# EMG_SS19_Version_1_0.net
KiCad netlist of a schematic drawn in EAGLE
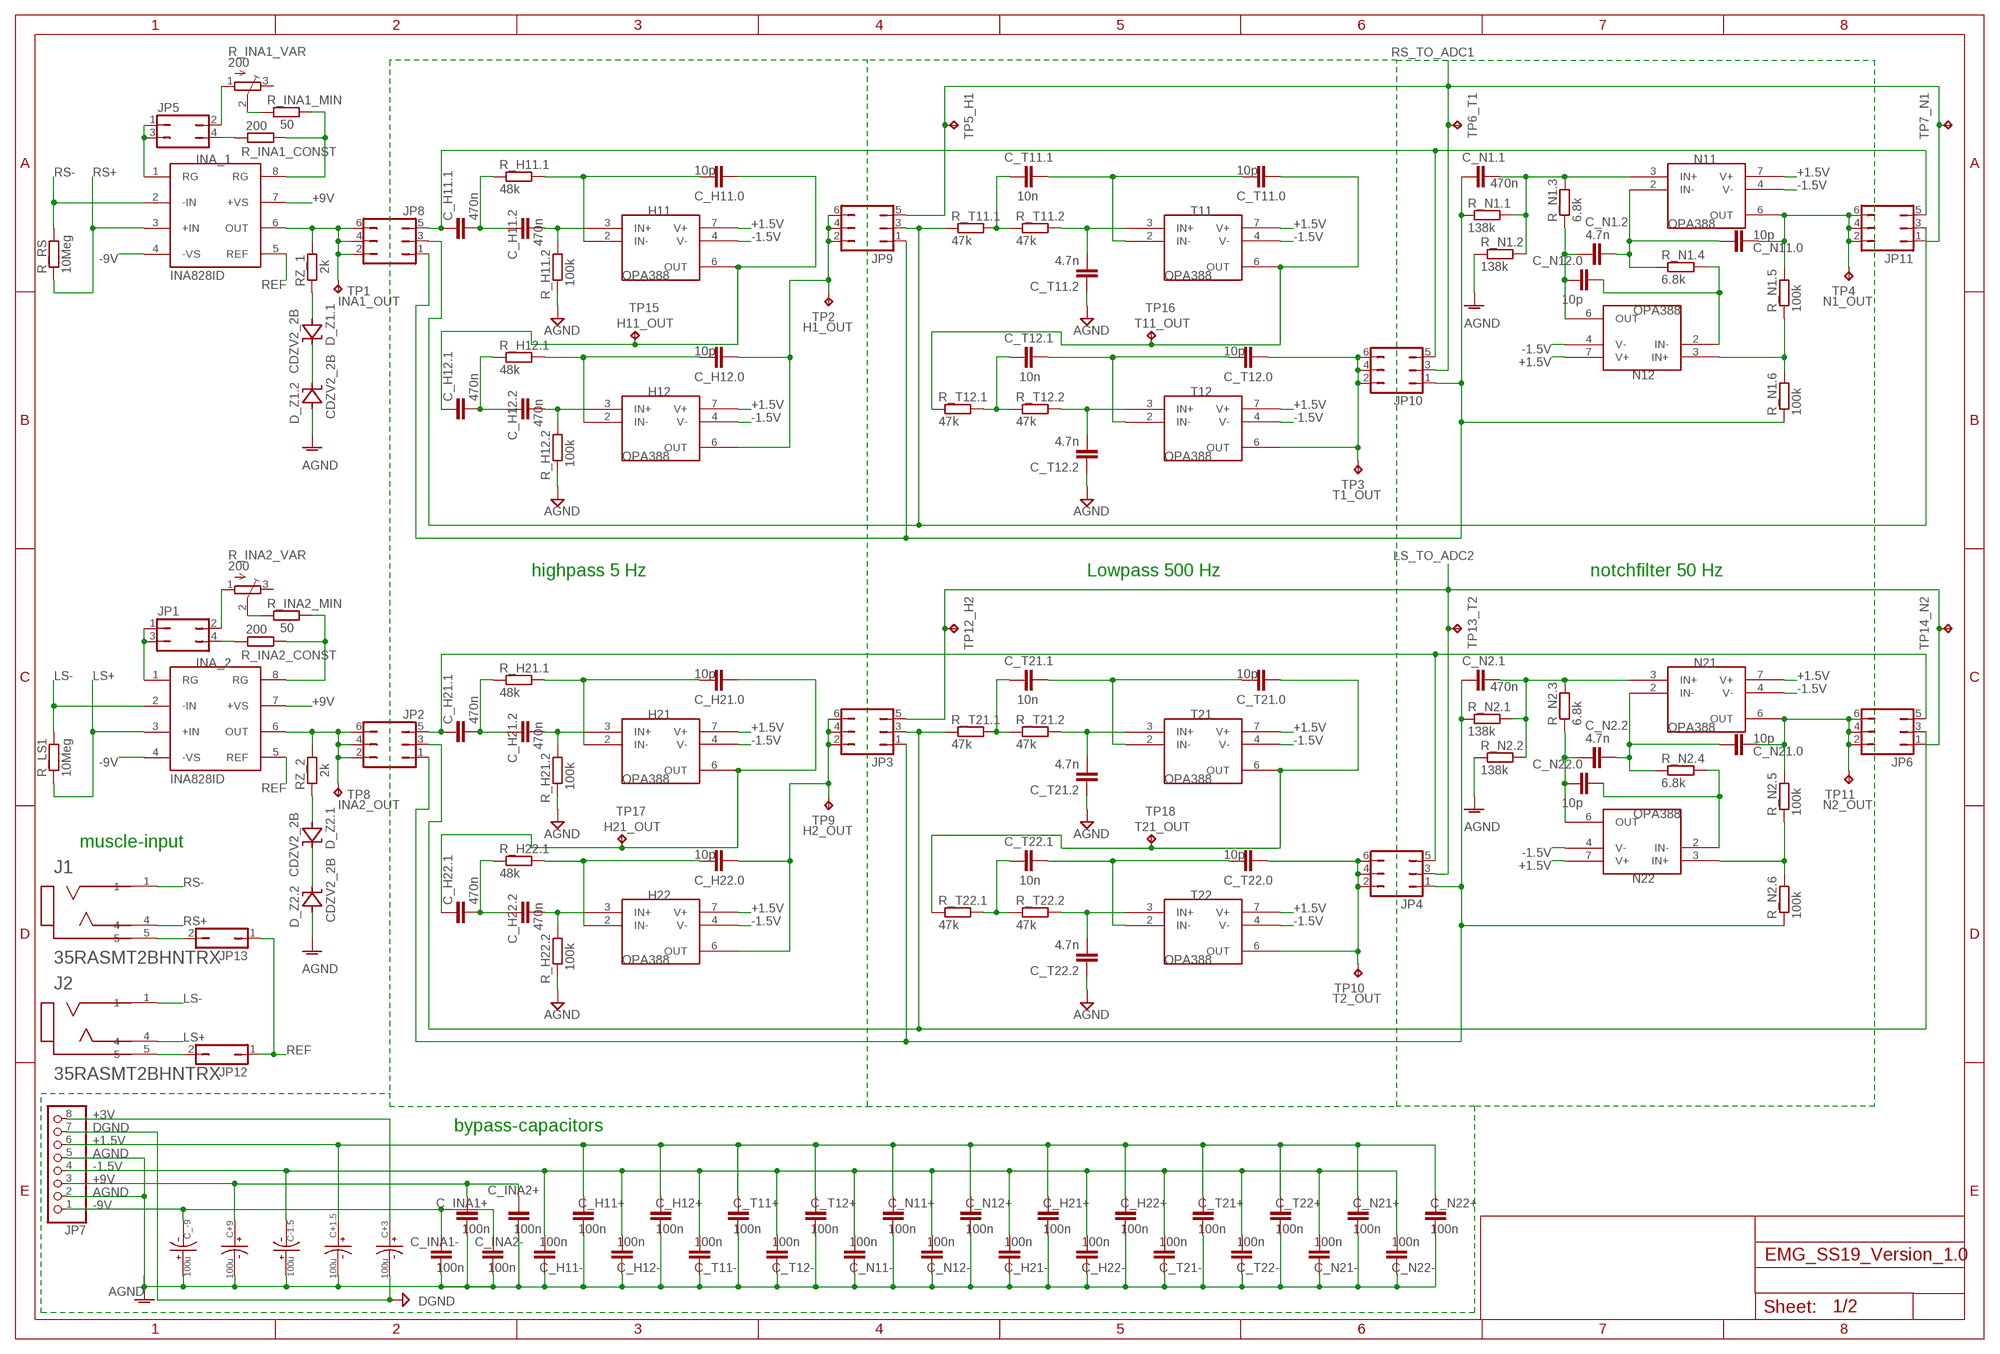
[diagram p0: schematic, sheet 1]
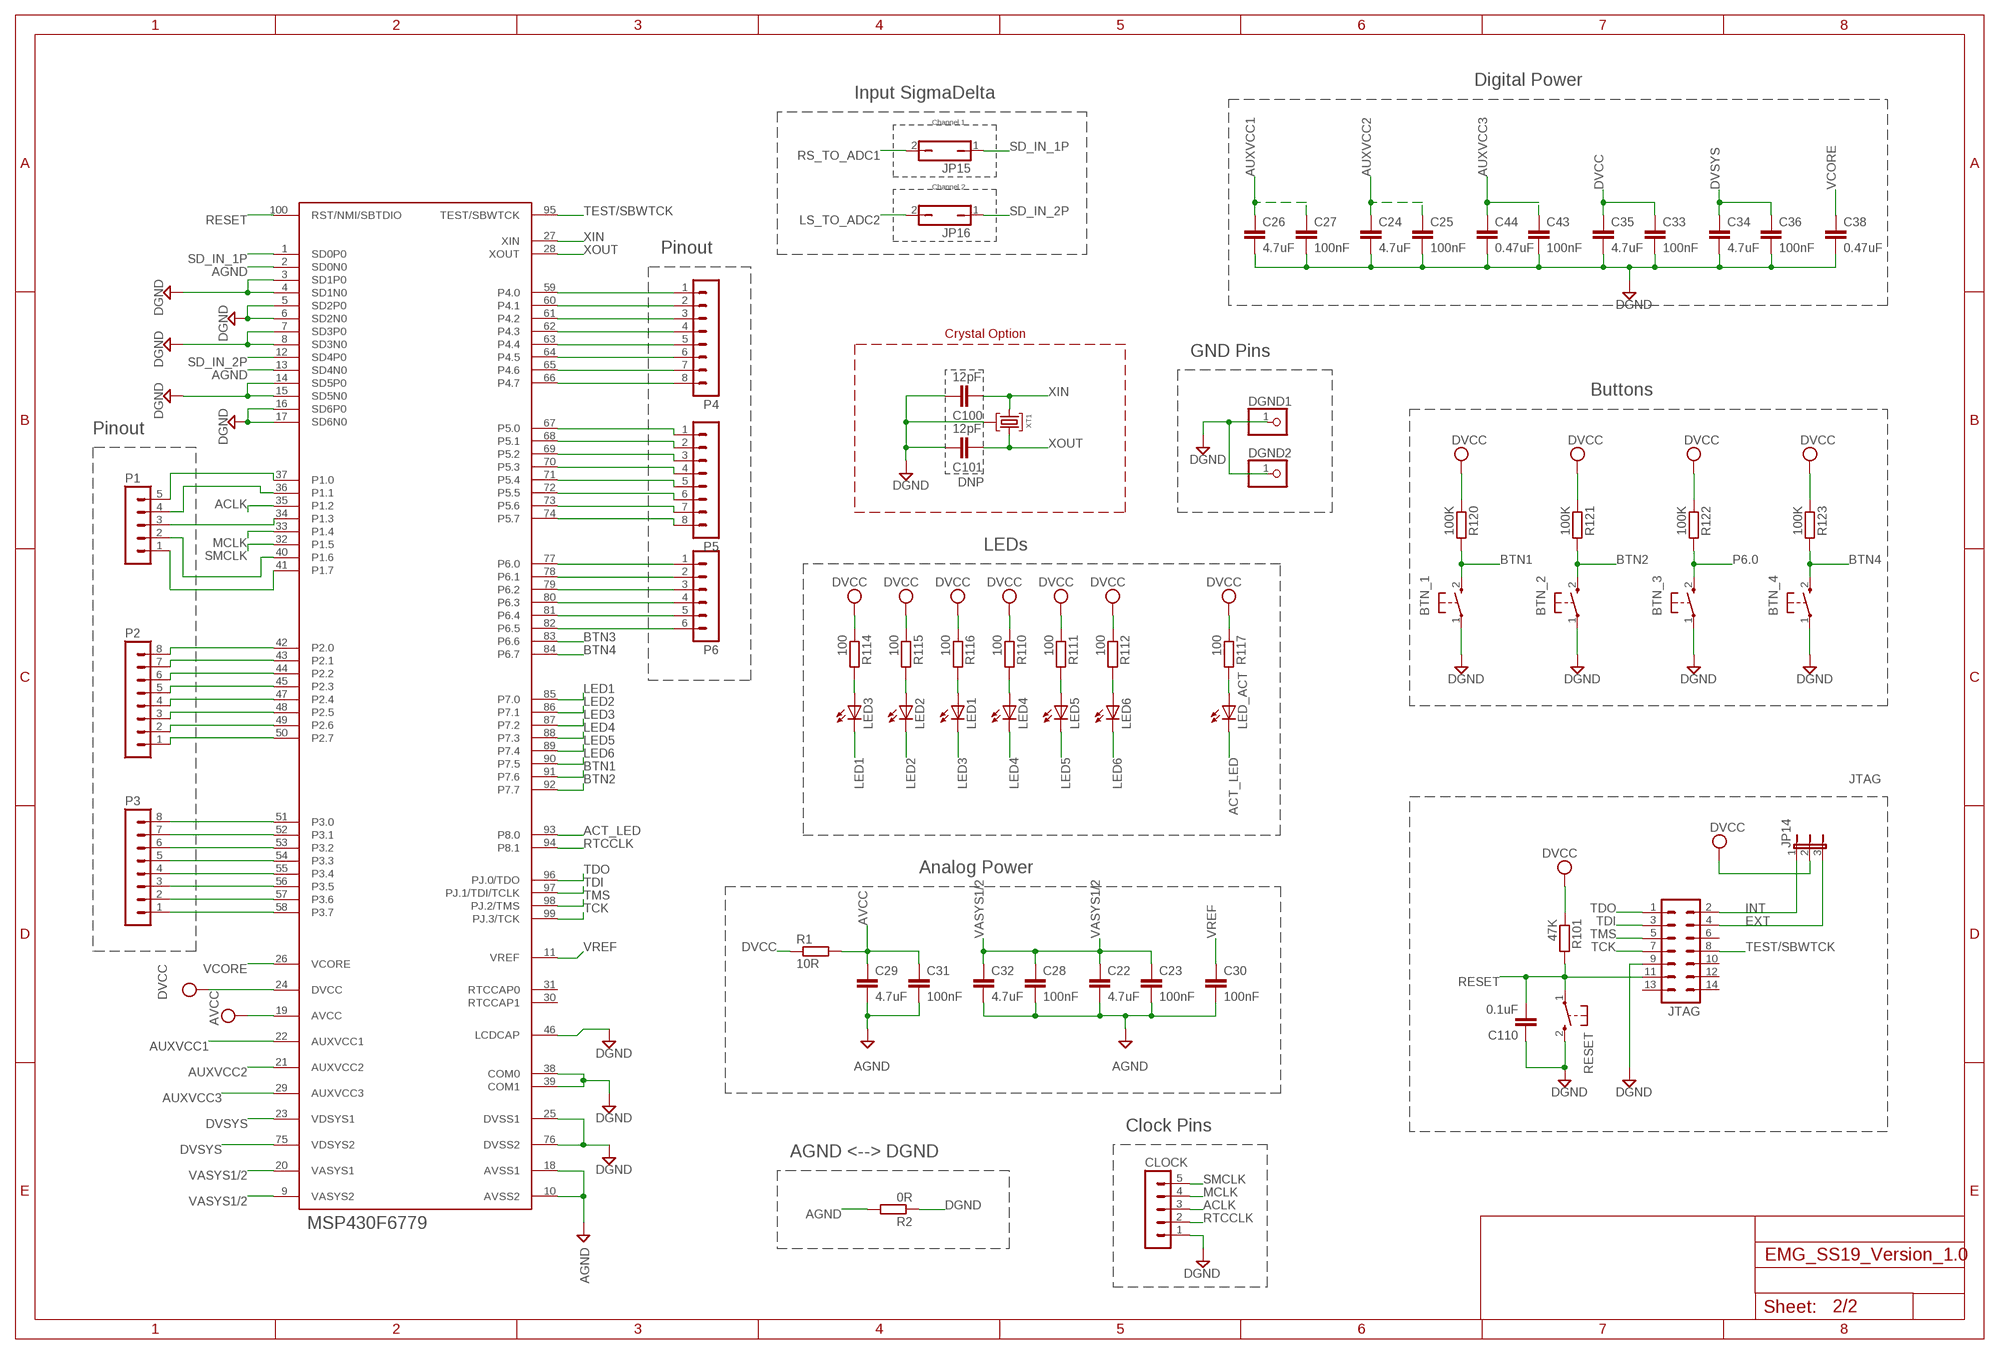
[diagram p1: schematic, sheet 2]

(export (version "E")
  (design (tool "Eeschema 10.0.6"))
  (components
    (comp (ref "C+1.5")
      (value "100u")
      (footprint "eagle-import:CAPPRD350W60D800H1150B")
      (fields (field (name "MF") "Panasonic Electronic") (field (name "MP") "ECA1HM101"))
      (libsource (lib "eagle-import") (part "ECA-1HM101"))
    )
    (comp (ref "C+3")
      (value "100u")
      (footprint "eagle-import:CAPPRD350W60D800H1150B")
      (fields (field (name "MF") "Panasonic Electronic") (field (name "MP") "ECA1HM101"))
      (libsource (lib "eagle-import") (part "ECA-1HM101"))
    )
    (comp (ref "C+9")
      (value "100u")
      (footprint "eagle-import:CAPPRD350W60D800H1150B")
      (fields (field (name "MF") "Panasonic Electronic") (field (name "MP") "ECA1HM101"))
      (libsource (lib "eagle-import") (part "ECA-1HM101"))
    )
    (comp (ref "C-1.5")
      (value "100u")
      (footprint "eagle-import:CAPPRD350W60D800H1150B")
      (fields (field (name "MF") "Panasonic Electronic") (field (name "MP") "ECA1HM101"))
      (libsource (lib "eagle-import") (part "ECA-1HM101"))
    )
    (comp (ref "C_-9")
      (value "100u")
      (footprint "eagle-import:CAPPRD350W60D800H1150B")
      (fields (field (name "MF") "Panasonic Electronic") (field (name "MP") "ECA1HM101"))
      (libsource (lib "eagle-import") (part "ECA-1HM101"))
    )
    (comp (ref "C_H11+")
      (value "100n")
      (footprint "eagle-import:C0805")
      (libsource (lib "eagle-import") (part "C-EUC0805"))
    )
    (comp (ref "C_H11-")
      (value "100n")
      (footprint "eagle-import:C0805")
      (libsource (lib "eagle-import") (part "C-EUC0805"))
    )
    (comp (ref "C_H11.0")
      (value "10p")
      (footprint "eagle-import:C0805")
      (libsource (lib "eagle-import") (part "C-EUC0805"))
    )
    (comp (ref "C_H11.1")
      (value "470n")
      (footprint "eagle-import:C0805")
      (libsource (lib "eagle-import") (part "C-EUC0805"))
    )
    (comp (ref "C_H11.2")
      (value "470n")
      (footprint "eagle-import:C0805")
      (libsource (lib "eagle-import") (part "C-EUC0805"))
    )
    (comp (ref "C_H12+")
      (value "100n")
      (footprint "eagle-import:C0805")
      (libsource (lib "eagle-import") (part "C-EUC0805"))
    )
    (comp (ref "C_H12-")
      (value "100n")
      (footprint "eagle-import:C0805")
      (libsource (lib "eagle-import") (part "C-EUC0805"))
    )
    (comp (ref "C_H12.0")
      (value "10p")
      (footprint "eagle-import:C0805")
      (libsource (lib "eagle-import") (part "C-EUC0805"))
    )
    (comp (ref "C_H12.1")
      (value "470n")
      (footprint "eagle-import:C0805")
      (libsource (lib "eagle-import") (part "C-EUC0805"))
    )
    (comp (ref "C_H12.2")
      (value "470n")
      (footprint "eagle-import:C0805")
      (libsource (lib "eagle-import") (part "C-EUC0805"))
    )
    (comp (ref "C_H21+")
      (value "100n")
      (footprint "eagle-import:C0805")
      (libsource (lib "eagle-import") (part "C-EUC0805"))
    )
    (comp (ref "C_H21-")
      (value "100n")
      (footprint "eagle-import:C0805")
      (libsource (lib "eagle-import") (part "C-EUC0805"))
    )
    (comp (ref "C_H21.0")
      (value "10p")
      (footprint "eagle-import:C0805")
      (libsource (lib "eagle-import") (part "C-EUC0805"))
    )
    (comp (ref "C_H21.1")
      (value "470n")
      (footprint "eagle-import:C0805")
      (libsource (lib "eagle-import") (part "C-EUC0805"))
    )
    (comp (ref "C_H21.2")
      (value "470n")
      (footprint "eagle-import:C0805")
      (libsource (lib "eagle-import") (part "C-EUC0805"))
    )
    (comp (ref "C_H22+")
      (value "100n")
      (footprint "eagle-import:C0805")
      (libsource (lib "eagle-import") (part "C-EUC0805"))
    )
    (comp (ref "C_H22-")
      (value "100n")
      (footprint "eagle-import:C0805")
      (libsource (lib "eagle-import") (part "C-EUC0805"))
    )
    (comp (ref "C_H22.0")
      (value "10p")
      (footprint "eagle-import:C0805")
      (libsource (lib "eagle-import") (part "C-EUC0805"))
    )
    (comp (ref "C_H22.1")
      (value "470n")
      (footprint "eagle-import:C0805")
      (libsource (lib "eagle-import") (part "C-EUC0805"))
    )
    (comp (ref "C_H22.2")
      (value "470n")
      (footprint "eagle-import:C0805")
      (libsource (lib "eagle-import") (part "C-EUC0805"))
    )
    (comp (ref "C_INA1+")
      (value "100n")
      (footprint "eagle-import:C0805")
      (libsource (lib "eagle-import") (part "C-EUC0805"))
    )
    (comp (ref "C_INA1-")
      (value "100n")
      (footprint "eagle-import:C0805")
      (libsource (lib "eagle-import") (part "C-EUC0805"))
    )
    (comp (ref "C_INA2+")
      (value "100n")
      (footprint "eagle-import:C0805")
      (libsource (lib "eagle-import") (part "C-EUC0805"))
    )
    (comp (ref "C_INA2-")
      (value "100n")
      (footprint "eagle-import:C0805")
      (libsource (lib "eagle-import") (part "C-EUC0805"))
    )
    (comp (ref "C_N1.1")
      (value "470n")
      (footprint "eagle-import:C0805")
      (libsource (lib "eagle-import") (part "C-EUC0805"))
    )
    (comp (ref "C_N1.2")
      (value "4.7n")
      (footprint "eagle-import:C0805")
      (libsource (lib "eagle-import") (part "C-EUC0805"))
    )
    (comp (ref "C_N2.1")
      (value "470n")
      (footprint "eagle-import:C0805")
      (libsource (lib "eagle-import") (part "C-EUC0805"))
    )
    (comp (ref "C_N2.2")
      (value "4.7n")
      (footprint "eagle-import:C0805")
      (libsource (lib "eagle-import") (part "C-EUC0805"))
    )
    (comp (ref "C_N11+")
      (value "100n")
      (footprint "eagle-import:C0805")
      (libsource (lib "eagle-import") (part "C-EUC0805"))
    )
    (comp (ref "C_N11-")
      (value "100n")
      (footprint "eagle-import:C0805")
      (libsource (lib "eagle-import") (part "C-EUC0805"))
    )
    (comp (ref "C_N11.0")
      (value "10p")
      (footprint "eagle-import:C0805")
      (libsource (lib "eagle-import") (part "C-EUC0805"))
    )
    (comp (ref "C_N12+")
      (value "100n")
      (footprint "eagle-import:C0805")
      (libsource (lib "eagle-import") (part "C-EUC0805"))
    )
    (comp (ref "C_N12-")
      (value "100n")
      (footprint "eagle-import:C0805")
      (libsource (lib "eagle-import") (part "C-EUC0805"))
    )
    (comp (ref "C_N12.0")
      (value "10p")
      (footprint "eagle-import:C0805")
      (libsource (lib "eagle-import") (part "C-EUC0805"))
    )
    (comp (ref "C_N21+")
      (value "100n")
      (footprint "eagle-import:C0805")
      (libsource (lib "eagle-import") (part "C-EUC0805"))
    )
    (comp (ref "C_N21-")
      (value "100n")
      (footprint "eagle-import:C0805")
      (libsource (lib "eagle-import") (part "C-EUC0805"))
    )
    (comp (ref "C_N21.0")
      (value "10p")
      (footprint "eagle-import:C0805")
      (libsource (lib "eagle-import") (part "C-EUC0805"))
    )
    (comp (ref "C_N22+")
      (value "100n")
      (footprint "eagle-import:C0805")
      (libsource (lib "eagle-import") (part "C-EUC0805"))
    )
    (comp (ref "C_N22-")
      (value "100n")
      (footprint "eagle-import:C0805")
      (libsource (lib "eagle-import") (part "C-EUC0805"))
    )
    (comp (ref "C_N22.0")
      (value "10p")
      (footprint "eagle-import:C0805")
      (libsource (lib "eagle-import") (part "C-EUC0805"))
    )
    (comp (ref "C_T11+")
      (value "100n")
      (footprint "eagle-import:C0805")
      (libsource (lib "eagle-import") (part "C-EUC0805"))
    )
    (comp (ref "C_T11-")
      (value "100n")
      (footprint "eagle-import:C0805")
      (libsource (lib "eagle-import") (part "C-EUC0805"))
    )
    (comp (ref "C_T11.0")
      (value "10p")
      (footprint "eagle-import:C0805")
      (libsource (lib "eagle-import") (part "C-EUC0805"))
    )
    (comp (ref "C_T11.1")
      (value "10n")
      (footprint "eagle-import:C0805")
      (libsource (lib "eagle-import") (part "C-EUC0805"))
    )
    (comp (ref "C_T11.2")
      (value "4.7n")
      (footprint "eagle-import:C0805")
      (libsource (lib "eagle-import") (part "C-EUC0805"))
    )
    (comp (ref "C_T12+")
      (value "100n")
      (footprint "eagle-import:C0805")
      (libsource (lib "eagle-import") (part "C-EUC0805"))
    )
    (comp (ref "C_T12-")
      (value "100n")
      (footprint "eagle-import:C0805")
      (libsource (lib "eagle-import") (part "C-EUC0805"))
    )
    (comp (ref "C_T12.0")
      (value "10p")
      (footprint "eagle-import:C0805")
      (libsource (lib "eagle-import") (part "C-EUC0805"))
    )
    (comp (ref "C_T12.1")
      (value "10n")
      (footprint "eagle-import:C0805")
      (libsource (lib "eagle-import") (part "C-EUC0805"))
    )
    (comp (ref "C_T12.2")
      (value "4.7n")
      (footprint "eagle-import:C0805")
      (libsource (lib "eagle-import") (part "C-EUC0805"))
    )
    (comp (ref "C_T21+")
      (value "100n")
      (footprint "eagle-import:C0805")
      (libsource (lib "eagle-import") (part "C-EUC0805"))
    )
    (comp (ref "C_T21-")
      (value "100n")
      (footprint "eagle-import:C0805")
      (libsource (lib "eagle-import") (part "C-EUC0805"))
    )
    (comp (ref "C_T21.0")
      (value "10p")
      (footprint "eagle-import:C0805")
      (libsource (lib "eagle-import") (part "C-EUC0805"))
    )
    (comp (ref "C_T21.1")
      (value "10n")
      (footprint "eagle-import:C0805")
      (libsource (lib "eagle-import") (part "C-EUC0805"))
    )
    (comp (ref "C_T21.2")
      (value "4.7n")
      (footprint "eagle-import:C0805")
      (libsource (lib "eagle-import") (part "C-EUC0805"))
    )
    (comp (ref "C_T22+")
      (value "100n")
      (footprint "eagle-import:C0805")
      (libsource (lib "eagle-import") (part "C-EUC0805"))
    )
    (comp (ref "C_T22-")
      (value "100n")
      (footprint "eagle-import:C0805")
      (libsource (lib "eagle-import") (part "C-EUC0805"))
    )
    (comp (ref "C_T22.0")
      (value "10p")
      (footprint "eagle-import:C0805")
      (libsource (lib "eagle-import") (part "C-EUC0805"))
    )
    (comp (ref "C_T22.1")
      (value "10n")
      (footprint "eagle-import:C0805")
      (libsource (lib "eagle-import") (part "C-EUC0805"))
    )
    (comp (ref "C_T22.2")
      (value "4.7n")
      (footprint "eagle-import:C0805")
      (libsource (lib "eagle-import") (part "C-EUC0805"))
    )
    (comp (ref "D_Z1.1")
      (value "CDZV2_2B")
      (footprint "eagle-import:SODFL1006X40N")
      (libsource (lib "eagle-import") (part "CDZV2_2BSOD923"))
    )
    (comp (ref "D_Z1.2")
      (value "CDZV2_2B")
      (footprint "eagle-import:SODFL1006X40N")
      (libsource (lib "eagle-import") (part "CDZV2_2BSOD923"))
    )
    (comp (ref "D_Z2.1")
      (value "CDZV2_2B")
      (footprint "eagle-import:SODFL1006X40N")
      (libsource (lib "eagle-import") (part "CDZV2_2BSOD923"))
    )
    (comp (ref "D_Z2.2")
      (value "CDZV2_2B")
      (footprint "eagle-import:SODFL1006X40N")
      (libsource (lib "eagle-import") (part "CDZV2_2BSOD923"))
    )
    (comp (ref "H11")
      (value "OPA388")
      (footprint "eagle-import:SOIC127P600X175-8N")
      (libsource (lib "eagle-import") (part "OPA388"))
    )
    (comp (ref "H12")
      (value "OPA388")
      (footprint "eagle-import:SOIC127P600X175-8N")
      (libsource (lib "eagle-import") (part "OPA388"))
    )
    (comp (ref "H21")
      (value "OPA388")
      (footprint "eagle-import:SOIC127P600X175-8N")
      (libsource (lib "eagle-import") (part "OPA388"))
    )
    (comp (ref "H22")
      (value "OPA388")
      (footprint "eagle-import:SOIC127P600X175-8N")
      (libsource (lib "eagle-import") (part "OPA388"))
    )
    (comp (ref "INA_1")
      (value "INA828ID")
      (footprint "eagle-import:SOIC8")
      (fields (field (name "DIGI-KEY_PART_NUMBER") "296-47415-ND") (field (name "MF") "Texas Instruments"))
      (libsource (lib "eagle-import") (part "INA828ID"))
    )
    (comp (ref "INA_2")
      (value "INA828ID")
      (footprint "eagle-import:SOIC8")
      (fields (field (name "DIGI-KEY_PART_NUMBER") "296-47415-ND") (field (name "MF") "Texas Instruments"))
      (libsource (lib "eagle-import") (part "INA828ID"))
    )
    (comp (ref "J1")
      (value "35RASMT2BHNTRX")
      (footprint "eagle-import:SWITCHCRAFT_35RASMT2BHNTRX")
      (fields (field (name "MF") "Switchcraft"))
      (libsource (lib "eagle-import") (part "35RASMT2BHNTRX"))
    )
    (comp (ref "J2")
      (value "35RASMT2BHNTRX")
      (footprint "eagle-import:SWITCHCRAFT_35RASMT2BHNTRX")
      (fields (field (name "MF") "Switchcraft"))
      (libsource (lib "eagle-import") (part "35RASMT2BHNTRX"))
    )
    (comp (ref "JP1")
      (value "JP2Q")
      (footprint "eagle-import:JP2Q")
      (libsource (lib "eagle-import") (part "JP2Q"))
    )
    (comp (ref "JP2")
      (value "JP3Q")
      (footprint "eagle-import:JP3Q")
      (libsource (lib "eagle-import") (part "JP3Q"))
    )
    (comp (ref "JP3")
      (value "JP3Q")
      (footprint "eagle-import:JP3Q")
      (libsource (lib "eagle-import") (part "JP3Q"))
    )
    (comp (ref "JP4")
      (value "JP3Q")
      (footprint "eagle-import:JP3Q")
      (libsource (lib "eagle-import") (part "JP3Q"))
    )
    (comp (ref "JP5")
      (value "JP2Q")
      (footprint "eagle-import:JP2Q")
      (libsource (lib "eagle-import") (part "JP2Q"))
    )
    (comp (ref "JP6")
      (value "JP3Q")
      (footprint "eagle-import:JP3Q")
      (libsource (lib "eagle-import") (part "JP3Q"))
    )
    (comp (ref "JP7")
      (value "PINHD-1X8")
      (footprint "eagle-import:1X08")
      (libsource (lib "eagle-import") (part "PINHD-1X8"))
    )
    (comp (ref "JP8")
      (value "JP3Q")
      (footprint "eagle-import:JP3Q")
      (libsource (lib "eagle-import") (part "JP3Q"))
    )
    (comp (ref "JP9")
      (value "JP3Q")
      (footprint "eagle-import:JP3Q")
      (libsource (lib "eagle-import") (part "JP3Q"))
    )
    (comp (ref "JP10")
      (value "JP3Q")
      (footprint "eagle-import:JP3Q")
      (libsource (lib "eagle-import") (part "JP3Q"))
    )
    (comp (ref "JP11")
      (value "JP3Q")
      (footprint "eagle-import:JP3Q")
      (libsource (lib "eagle-import") (part "JP3Q"))
    )
    (comp (ref "JP12")
      (value "JP1Q")
      (footprint "eagle-import:JP1")
      (libsource (lib "eagle-import") (part "JP1Q"))
    )
    (comp (ref "JP13")
      (value "JP1Q")
      (footprint "eagle-import:JP1")
      (libsource (lib "eagle-import") (part "JP1Q"))
    )
    (comp (ref "N11")
      (value "OPA388")
      (footprint "eagle-import:SOIC127P600X175-8N")
      (libsource (lib "eagle-import") (part "OPA388"))
    )
    (comp (ref "N12")
      (value "OPA388")
      (footprint "eagle-import:SOIC127P600X175-8N")
      (libsource (lib "eagle-import") (part "OPA388"))
    )
    (comp (ref "N21")
      (value "OPA388")
      (footprint "eagle-import:SOIC127P600X175-8N")
      (libsource (lib "eagle-import") (part "OPA388"))
    )
    (comp (ref "N22")
      (value "OPA388")
      (footprint "eagle-import:SOIC127P600X175-8N")
      (libsource (lib "eagle-import") (part "OPA388"))
    )
    (comp (ref "RZ_1")
      (value "2k")
      (footprint "eagle-import:R0805")
      (libsource (lib "eagle-import") (part "R-EU_R0805"))
    )
    (comp (ref "RZ_2")
      (value "2k")
      (footprint "eagle-import:R0805")
      (libsource (lib "eagle-import") (part "R-EU_R0805"))
    )
    (comp (ref "R_H11.1")
      (value "48k")
      (footprint "eagle-import:R0805")
      (libsource (lib "eagle-import") (part "R-EU_R0805"))
    )
    (comp (ref "R_H11.2")
      (value "100k")
      (footprint "eagle-import:R0805")
      (libsource (lib "eagle-import") (part "R-EU_R0805"))
    )
    (comp (ref "R_H12.1")
      (value "48k")
      (footprint "eagle-import:R0805")
      (libsource (lib "eagle-import") (part "R-EU_R0805"))
    )
    (comp (ref "R_H12.2")
      (value "100k")
      (footprint "eagle-import:R0805")
      (libsource (lib "eagle-import") (part "R-EU_R0805"))
    )
    (comp (ref "R_H21.1")
      (value "48k")
      (footprint "eagle-import:R0805")
      (libsource (lib "eagle-import") (part "R-EU_R0805"))
    )
    (comp (ref "R_H21.2")
      (value "100k")
      (footprint "eagle-import:R0805")
      (libsource (lib "eagle-import") (part "R-EU_R0805"))
    )
    (comp (ref "R_H22.1")
      (value "48k")
      (footprint "eagle-import:R0805")
      (libsource (lib "eagle-import") (part "R-EU_R0805"))
    )
    (comp (ref "R_H22.2")
      (value "100k")
      (footprint "eagle-import:R0805")
      (libsource (lib "eagle-import") (part "R-EU_R0805"))
    )
    (comp (ref "R_INA1_CONST")
      (value "200")
      (footprint "eagle-import:R0805")
      (libsource (lib "eagle-import") (part "R-EU_R0805"))
    )
    (comp (ref "R_INA1_MIN")
      (value "50")
      (footprint "eagle-import:R0805")
      (libsource (lib "eagle-import") (part "R-EU_R0805"))
    )
    (comp (ref "R_INA1_VAR")
      (value "200")
      (footprint "eagle-import:SM-42_43W")
      (fields (field (name "SPICEPREFIX") "J"))
      (libsource (lib "eagle-import") (part "TRIM_EU-SM-42/43W"))
    )
    (comp (ref "R_INA2_CONST")
      (value "200")
      (footprint "eagle-import:R0805")
      (libsource (lib "eagle-import") (part "R-EU_R0805"))
    )
    (comp (ref "R_INA2_MIN")
      (value "50")
      (footprint "eagle-import:R0805")
      (libsource (lib "eagle-import") (part "R-EU_R0805"))
    )
    (comp (ref "R_INA2_VAR")
      (value "200")
      (footprint "eagle-import:SM-42_43W")
      (fields (field (name "SPICEPREFIX") "J"))
      (libsource (lib "eagle-import") (part "TRIM_EU-SM-42/43W"))
    )
    (comp (ref "R_LS1")
      (value "10Meg")
      (footprint "eagle-import:R0805")
      (libsource (lib "eagle-import") (part "R-EU_R0805"))
    )
    (comp (ref "R_N1.1")
      (value "138k")
      (footprint "eagle-import:R0805")
      (libsource (lib "eagle-import") (part "R-EU_R0805"))
    )
    (comp (ref "R_N1.2")
      (value "138k")
      (footprint "eagle-import:R0805")
      (libsource (lib "eagle-import") (part "R-EU_R0805"))
    )
    (comp (ref "R_N1.3")
      (value "6.8k")
      (footprint "eagle-import:R0805")
      (libsource (lib "eagle-import") (part "R-EU_R0805"))
    )
    (comp (ref "R_N1.4")
      (value "6.8k")
      (footprint "eagle-import:R0805")
      (libsource (lib "eagle-import") (part "R-EU_R0805"))
    )
    (comp (ref "R_N1.5")
      (value "100k")
      (footprint "eagle-import:R0805")
      (libsource (lib "eagle-import") (part "R-EU_R0805"))
    )
    (comp (ref "R_N1.6")
      (value "100k")
      (footprint "eagle-import:R0805")
      (libsource (lib "eagle-import") (part "R-EU_R0805"))
    )
    (comp (ref "R_N2.1")
      (value "138k")
      (footprint "eagle-import:R0805")
      (libsource (lib "eagle-import") (part "R-EU_R0805"))
    )
    (comp (ref "R_N2.2")
      (value "138k")
      (footprint "eagle-import:R0805")
      (libsource (lib "eagle-import") (part "R-EU_R0805"))
    )
    (comp (ref "R_N2.3")
      (value "6.8k")
      (footprint "eagle-import:R0805")
      (libsource (lib "eagle-import") (part "R-EU_R0805"))
    )
    (comp (ref "R_N2.4")
      (value "6.8k")
      (footprint "eagle-import:R0805")
      (libsource (lib "eagle-import") (part "R-EU_R0805"))
    )
    (comp (ref "R_N2.5")
      (value "100k")
      (footprint "eagle-import:R0805")
      (libsource (lib "eagle-import") (part "R-EU_R0805"))
    )
    (comp (ref "R_N2.6")
      (value "100k")
      (footprint "eagle-import:R0805")
      (libsource (lib "eagle-import") (part "R-EU_R0805"))
    )
    (comp (ref "R_RS")
      (value "10Meg")
      (footprint "eagle-import:R0805")
      (libsource (lib "eagle-import") (part "R-EU_R0805"))
    )
    (comp (ref "R_T11.1")
      (value "47k")
      (footprint "eagle-import:R0805")
      (libsource (lib "eagle-import") (part "R-EU_R0805"))
    )
    (comp (ref "R_T11.2")
      (value "47k")
      (footprint "eagle-import:R0805")
      (libsource (lib "eagle-import") (part "R-EU_R0805"))
    )
    (comp (ref "R_T12.1")
      (value "47k")
      (footprint "eagle-import:R0805")
      (libsource (lib "eagle-import") (part "R-EU_R0805"))
    )
    (comp (ref "R_T12.2")
      (value "47k")
      (footprint "eagle-import:R0805")
      (libsource (lib "eagle-import") (part "R-EU_R0805"))
    )
    (comp (ref "R_T21.1")
      (value "47k")
      (footprint "eagle-import:R0805")
      (libsource (lib "eagle-import") (part "R-EU_R0805"))
    )
    (comp (ref "R_T21.2")
      (value "47k")
      (footprint "eagle-import:R0805")
      (libsource (lib "eagle-import") (part "R-EU_R0805"))
    )
    (comp (ref "R_T22.1")
      (value "47k")
      (footprint "eagle-import:R0805")
      (libsource (lib "eagle-import") (part "R-EU_R0805"))
    )
    (comp (ref "R_T22.2")
      (value "47k")
      (footprint "eagle-import:R0805")
      (libsource (lib "eagle-import") (part "R-EU_R0805"))
    )
    (comp (ref "T11")
      (value "OPA388")
      (footprint "eagle-import:SOIC127P600X175-8N")
      (libsource (lib "eagle-import") (part "OPA388"))
    )
    (comp (ref "T12")
      (value "OPA388")
      (footprint "eagle-import:SOIC127P600X175-8N")
      (libsource (lib "eagle-import") (part "OPA388"))
    )
    (comp (ref "T21")
      (value "OPA388")
      (footprint "eagle-import:SOIC127P600X175-8N")
      (libsource (lib "eagle-import") (part "OPA388"))
    )
    (comp (ref "T22")
      (value "OPA388")
      (footprint "eagle-import:SOIC127P600X175-8N")
      (libsource (lib "eagle-import") (part "OPA388"))
    )
    (comp (ref "TP1")
      (value "TPPAD1-13")
      (footprint "eagle-import:P1-13")
      (libsource (lib "eagle-import") (part "TPPAD1-13"))
    )
    (comp (ref "TP2")
      (value "TPPAD1-13")
      (footprint "eagle-import:P1-13")
      (libsource (lib "eagle-import") (part "TPPAD1-13"))
    )
    (comp (ref "TP3")
      (value "TPPAD1-13")
      (footprint "eagle-import:P1-13")
      (libsource (lib "eagle-import") (part "TPPAD1-13"))
    )
    (comp (ref "TP4")
      (value "TPPAD1-13")
      (footprint "eagle-import:P1-13")
      (libsource (lib "eagle-import") (part "TPPAD1-13"))
    )
    (comp (ref "TP5_H1")
      (value "TPPAD1-13")
      (footprint "eagle-import:P1-13")
      (libsource (lib "eagle-import") (part "TPPAD1-13"))
    )
    (comp (ref "TP6_T1")
      (value "TPPAD1-13")
      (footprint "eagle-import:P1-13")
      (libsource (lib "eagle-import") (part "TPPAD1-13"))
    )
    (comp (ref "TP7_N1")
      (value "TPPAD1-13")
      (footprint "eagle-import:P1-13")
      (libsource (lib "eagle-import") (part "TPPAD1-13"))
    )
    (comp (ref "TP8")
      (value "TPPAD1-13")
      (footprint "eagle-import:P1-13")
      (libsource (lib "eagle-import") (part "TPPAD1-13"))
    )
    (comp (ref "TP9")
      (value "TPPAD1-13")
      (footprint "eagle-import:P1-13")
      (libsource (lib "eagle-import") (part "TPPAD1-13"))
    )
    (comp (ref "TP10")
      (value "TPPAD1-13")
      (footprint "eagle-import:P1-13")
      (libsource (lib "eagle-import") (part "TPPAD1-13"))
    )
    (comp (ref "TP11")
      (value "TPPAD1-13")
      (footprint "eagle-import:P1-13")
      (libsource (lib "eagle-import") (part "TPPAD1-13"))
    )
    (comp (ref "TP12_H2")
      (value "TPPAD1-13")
      (footprint "eagle-import:P1-13")
      (libsource (lib "eagle-import") (part "TPPAD1-13"))
    )
    (comp (ref "TP13_T2")
      (value "TPPAD1-13")
      (footprint "eagle-import:P1-13")
      (libsource (lib "eagle-import") (part "TPPAD1-13"))
    )
    (comp (ref "TP14_N2")
      (value "TPPAD1-13")
      (footprint "eagle-import:P1-13")
      (libsource (lib "eagle-import") (part "TPPAD1-13"))
    )
    (comp (ref "TP15")
      (value "TPPAD1-13")
      (footprint "eagle-import:P1-13")
      (libsource (lib "eagle-import") (part "TPPAD1-13"))
    )
    (comp (ref "TP16")
      (value "TPPAD1-13")
      (footprint "eagle-import:P1-13")
      (libsource (lib "eagle-import") (part "TPPAD1-13"))
    )
    (comp (ref "TP17")
      (value "TPPAD1-13")
      (footprint "eagle-import:P1-13")
      (libsource (lib "eagle-import") (part "TPPAD1-13"))
    )
    (comp (ref "TP18")
      (value "TPPAD1-13")
      (footprint "eagle-import:P1-13")
      (libsource (lib "eagle-import") (part "TPPAD1-13"))
    )
    (comp (ref "BTN_1")
      (value "PB")
      (footprint "eagle-import:PBTH")
      (libsource (lib "eagle-import") (part "PB"))
    )
    (comp (ref "BTN_2")
      (value "PB")
      (footprint "eagle-import:PBTH")
      (libsource (lib "eagle-import") (part "PB"))
    )
    (comp (ref "BTN_3")
      (value "PB")
      (footprint "eagle-import:PBTH")
      (libsource (lib "eagle-import") (part "PB"))
    )
    (comp (ref "BTN_4")
      (value "PB")
      (footprint "eagle-import:PBTH")
      (libsource (lib "eagle-import") (part "PB"))
    )
    (comp (ref "C22")
      (value "4.7uF")
      (footprint "eagle-import:C0805")
      (libsource (lib "eagle-import") (part "resistor_C-EUC0805"))
    )
    (comp (ref "C23")
      (value "100nF")
      (footprint "eagle-import:C0805")
      (libsource (lib "eagle-import") (part "resistor_C-EUC0805"))
    )
    (comp (ref "C24")
      (value "4.7uF")
      (footprint "eagle-import:C0805")
      (libsource (lib "eagle-import") (part "resistor_C-EUC0805"))
    )
    (comp (ref "C25")
      (value "100nF")
      (footprint "eagle-import:C0805")
      (libsource (lib "eagle-import") (part "resistor_C-EUC0805"))
    )
    (comp (ref "C26")
      (value "4.7uF")
      (footprint "eagle-import:C0805")
      (libsource (lib "eagle-import") (part "resistor_C-EUC0805"))
    )
    (comp (ref "C27")
      (value "100nF")
      (footprint "eagle-import:C0805")
      (libsource (lib "eagle-import") (part "resistor_C-EUC0805"))
    )
    (comp (ref "C28")
      (value "100nF")
      (footprint "eagle-import:C0805")
      (libsource (lib "eagle-import") (part "resistor_C-EUC0805"))
    )
    (comp (ref "C29")
      (value "4.7uF")
      (footprint "eagle-import:C0805")
      (libsource (lib "eagle-import") (part "resistor_C-EUC0805"))
    )
    (comp (ref "C30")
      (value "100nF")
      (footprint "eagle-import:C0805")
      (libsource (lib "eagle-import") (part "resistor_C-EUC0805"))
    )
    (comp (ref "C31")
      (value "100nF")
      (footprint "eagle-import:C0805")
      (libsource (lib "eagle-import") (part "resistor_C-EUC0805"))
    )
    (comp (ref "C32")
      (value "4.7uF")
      (footprint "eagle-import:C0805")
      (libsource (lib "eagle-import") (part "resistor_C-EUC0805"))
    )
    (comp (ref "C33")
      (value "100nF")
      (footprint "eagle-import:C0805")
      (libsource (lib "eagle-import") (part "resistor_C-EUC0805"))
    )
    (comp (ref "C34")
      (value "4.7uF")
      (footprint "eagle-import:C0805")
      (libsource (lib "eagle-import") (part "resistor_C-EUC0805"))
    )
    (comp (ref "C35")
      (value "4.7uF")
      (footprint "eagle-import:C0805")
      (libsource (lib "eagle-import") (part "resistor_C-EUC0805"))
    )
    (comp (ref "C36")
      (value "100nF")
      (footprint "eagle-import:C0805")
      (libsource (lib "eagle-import") (part "resistor_C-EUC0805"))
    )
    (comp (ref "C38")
      (value "0.47uF")
      (footprint "eagle-import:C0805")
      (libsource (lib "eagle-import") (part "resistor_C-EUC0805"))
    )
    (comp (ref "C43")
      (value "100nF")
      (footprint "eagle-import:C0805")
      (libsource (lib "eagle-import") (part "resistor_C-EUC0805"))
    )
    (comp (ref "C44")
      (value "0.47uF")
      (footprint "eagle-import:C0805")
      (libsource (lib "eagle-import") (part "resistor_C-EUC0805"))
    )
    (comp (ref "C100")
      (value "12pF")
      (footprint "eagle-import:C0805")
      (libsource (lib "eagle-import") (part "resistor_C-EUC0805"))
    )
    (comp (ref "C101")
      (value "12pF")
      (footprint "eagle-import:C0805")
      (libsource (lib "eagle-import") (part "resistor_C-EUC0805"))
    )
    (comp (ref "C110")
      (value "0.1uF")
      (footprint "eagle-import:C0805")
      (libsource (lib "eagle-import") (part "resistor_C-EUC0805"))
    )
    (comp (ref "CLOCK")
      (value "MA05-1")
      (footprint "eagle-import:MA05-1")
      (libsource (lib "eagle-import") (part "MA05-1"))
    )
    (comp (ref "DGND1")
      (value "PINHD-1X1")
      (footprint "eagle-import:1X01")
      (libsource (lib "eagle-import") (part "PINHD-1X1"))
    )
    (comp (ref "DGND2")
      (value "PINHD-1X1")
      (footprint "eagle-import:1X01")
      (libsource (lib "eagle-import") (part "PINHD-1X1"))
    )
    (comp (ref "JP14")
      (value "JP2E")
      (footprint "eagle-import:JP2")
      (libsource (lib "eagle-import") (part "JP2E"))
    )
    (comp (ref "JP15")
      (value "JP1Q")
      (footprint "eagle-import:JP1")
      (libsource (lib "eagle-import") (part "JP1Q"))
    )
    (comp (ref "JP16")
      (value "JP1Q")
      (footprint "eagle-import:JP1")
      (libsource (lib "eagle-import") (part "JP1Q"))
    )
    (comp (ref "JTAG")
      (value "ML14")
      (footprint "eagle-import:ML14")
      (libsource (lib "eagle-import") (part "ML14"))
    )
    (comp (ref "LED1")
      (value "LED3MM")
      (footprint "eagle-import:LED3MM")
      (libsource (lib "eagle-import") (part "LED3MM"))
    )
    (comp (ref "LED2")
      (value "LED3MM")
      (footprint "eagle-import:LED3MM")
      (libsource (lib "eagle-import") (part "LED3MM"))
    )
    (comp (ref "LED3")
      (value "LED3MM")
      (footprint "eagle-import:LED3MM")
      (libsource (lib "eagle-import") (part "LED3MM"))
    )
    (comp (ref "LED4")
      (value "LED3MM")
      (footprint "eagle-import:LED3MM")
      (libsource (lib "eagle-import") (part "LED3MM"))
    )
    (comp (ref "LED5")
      (value "LED3MM")
      (footprint "eagle-import:LED3MM")
      (libsource (lib "eagle-import") (part "LED3MM"))
    )
    (comp (ref "LED6")
      (value "LED3MM")
      (footprint "eagle-import:LED3MM")
      (libsource (lib "eagle-import") (part "LED3MM"))
    )
    (comp (ref "LED_ACT")
      (value "LED3MM")
      (footprint "eagle-import:LED3MM")
      (libsource (lib "eagle-import") (part "LED3MM"))
    )
    (comp (ref "P1")
      (value "MA05-1")
      (footprint "eagle-import:MA05-1")
      (libsource (lib "eagle-import") (part "con-lstb_162_MA05-1"))
    )
    (comp (ref "P2")
      (value "MA08-1")
      (footprint "eagle-import:MA08-1")
      (libsource (lib "eagle-import") (part "MA08-1"))
    )
    (comp (ref "P3")
      (value "MA08-1")
      (footprint "eagle-import:MA08-1")
      (libsource (lib "eagle-import") (part "MA08-1"))
    )
    (comp (ref "P4")
      (value "MA08-1")
      (footprint "eagle-import:MA08-1")
      (libsource (lib "eagle-import") (part "MA08-1"))
    )
    (comp (ref "P5")
      (value "MA08-1")
      (footprint "eagle-import:MA08-1")
      (libsource (lib "eagle-import") (part "MA08-1"))
    )
    (comp (ref "P6")
      (value "MA06-1")
      (footprint "eagle-import:MA06-1")
      (libsource (lib "eagle-import") (part "MA06-1"))
    )
    (comp (ref "R1")
      (value "10R")
      (footprint "eagle-import:R0805")
      (libsource (lib "eagle-import") (part "resistor_R-EU_R0805"))
    )
    (comp (ref "R2")
      (value "0R")
      (footprint "eagle-import:R0805")
      (libsource (lib "eagle-import") (part "resistor_R-EU_R0805"))
    )
    (comp (ref "R101")
      (value "47K")
      (footprint "eagle-import:R0805")
      (libsource (lib "eagle-import") (part "resistor_R-EU_R0805"))
    )
    (comp (ref "R110")
      (value "100")
      (footprint "eagle-import:R0805")
      (libsource (lib "eagle-import") (part "resistor_R-EU_R0805"))
    )
    (comp (ref "R111")
      (value "100")
      (footprint "eagle-import:R0805")
      (libsource (lib "eagle-import") (part "resistor_R-EU_R0805"))
    )
    (comp (ref "R112")
      (value "100")
      (footprint "eagle-import:R0805")
      (libsource (lib "eagle-import") (part "resistor_R-EU_R0805"))
    )
    (comp (ref "R114")
      (value "100")
      (footprint "eagle-import:R0805")
      (libsource (lib "eagle-import") (part "resistor_R-EU_R0805"))
    )
    (comp (ref "R115")
      (value "100")
      (footprint "eagle-import:R0805")
      (libsource (lib "eagle-import") (part "resistor_R-EU_R0805"))
    )
    (comp (ref "R116")
      (value "100")
      (footprint "eagle-import:R0805")
      (libsource (lib "eagle-import") (part "resistor_R-EU_R0805"))
    )
    (comp (ref "R117")
      (value "100")
      (footprint "eagle-import:R0805")
      (libsource (lib "eagle-import") (part "resistor_R-EU_R0805"))
    )
    (comp (ref "R120")
      (value "100K")
      (footprint "eagle-import:R0805")
      (libsource (lib "eagle-import") (part "resistor_R-EU_R0805"))
    )
    (comp (ref "R121")
      (value "100K")
      (footprint "eagle-import:R0805")
      (libsource (lib "eagle-import") (part "resistor_R-EU_R0805"))
    )
    (comp (ref "R122")
      (value "100K")
      (footprint "eagle-import:R0805")
      (libsource (lib "eagle-import") (part "resistor_R-EU_R0805"))
    )
    (comp (ref "R123")
      (value "100K")
      (footprint "eagle-import:R0805")
      (libsource (lib "eagle-import") (part "resistor_R-EU_R0805"))
    )
    (comp (ref "RESET")
      (value "RESET")
      (footprint "eagle-import:PBTH")
      (libsource (lib "eagle-import") (part "PB"))
    )
    (comp (ref "U$1")
      (value "MSP430F6779PZ")
      (footprint "eagle-import:S-PQFP-G100(PZ)")
      (libsource (lib "eagle-import") (part "MSP430F6779PZ"))
    )
    (comp (ref "XT1")
      (value "CM200T")
      (footprint "eagle-import:CM200T")
      (libsource (lib "eagle-import") (part "CM200T"))
    )
  )
  (nets
    (net (code "1") (name "+1.5V") (class "Default")
      (node (ref "C+1.5") (pin "+") (pinfunction "+_+") (pintype "passive"))
      (node (ref "C_H11+") (pin "1") (pinfunction "1_1") (pintype "passive"))
      (node (ref "C_H12+") (pin "1") (pinfunction "1_1") (pintype "passive"))
      (node (ref "C_H21+") (pin "1") (pinfunction "1_1") (pintype "passive"))
      (node (ref "C_H22+") (pin "1") (pinfunction "1_1") (pintype "passive"))
      (node (ref "C_N11+") (pin "1") (pinfunction "1_1") (pintype "passive"))
      (node (ref "C_N12+") (pin "1") (pinfunction "1_1") (pintype "passive"))
      (node (ref "C_N21+") (pin "1") (pinfunction "1_1") (pintype "passive"))
      (node (ref "C_N22+") (pin "1") (pinfunction "1_1") (pintype "passive"))
      (node (ref "C_T11+") (pin "1") (pinfunction "1_1") (pintype "passive"))
      (node (ref "C_T12+") (pin "1") (pinfunction "1_1") (pintype "passive"))
      (node (ref "C_T21+") (pin "1") (pinfunction "1_1") (pintype "passive"))
      (node (ref "C_T22+") (pin "1") (pinfunction "1_1") (pintype "passive"))
      (node (ref "H11") (pin "7") (pinfunction "V+_7") (pintype "power_in"))
      (node (ref "H12") (pin "7") (pinfunction "V+_7") (pintype "power_in"))
      (node (ref "H21") (pin "7") (pinfunction "V+_7") (pintype "power_in"))
      (node (ref "H22") (pin "7") (pinfunction "V+_7") (pintype "power_in"))
      (node (ref "JP7") (pin "6") (pinfunction "6_6") (pintype "passive"))
      (node (ref "N11") (pin "7") (pinfunction "V+_7") (pintype "power_in"))
      (node (ref "N12") (pin "7") (pinfunction "V+_7") (pintype "power_in"))
      (node (ref "N21") (pin "7") (pinfunction "V+_7") (pintype "power_in"))
      (node (ref "N22") (pin "7") (pinfunction "V+_7") (pintype "power_in"))
      (node (ref "T11") (pin "7") (pinfunction "V+_7") (pintype "power_in"))
      (node (ref "T12") (pin "7") (pinfunction "V+_7") (pintype "power_in"))
      (node (ref "T21") (pin "7") (pinfunction "V+_7") (pintype "power_in"))
      (node (ref "T22") (pin "7") (pinfunction "V+_7") (pintype "power_in"))
    )
    (net (code "2") (name "+3V") (class "Default")
      (node (ref "C+3") (pin "+") (pinfunction "+_+") (pintype "passive"))
      (node (ref "JP7") (pin "8") (pinfunction "8_8") (pintype "passive"))
    )
    (net (code "3") (name "+9V") (class "Default")
      (node (ref "C+9") (pin "+") (pinfunction "+_+") (pintype "passive"))
      (node (ref "C_INA1+") (pin "1") (pinfunction "1_1") (pintype "passive"))
      (node (ref "C_INA2+") (pin "1") (pinfunction "1_1") (pintype "passive"))
      (node (ref "INA_1") (pin "7") (pinfunction "+VS_7") (pintype "bidirectional"))
      (node (ref "INA_2") (pin "7") (pinfunction "+VS_7") (pintype "bidirectional"))
      (node (ref "JP7") (pin "3") (pinfunction "3_3") (pintype "passive"))
    )
    (net (code "4") (name "-1.5V") (class "Default")
      (node (ref "C-1.5") (pin "-") (pinfunction "-_-") (pintype "passive"))
      (node (ref "C_H11-") (pin "2") (pinfunction "2_2") (pintype "passive"))
      (node (ref "C_H12-") (pin "2") (pinfunction "2_2") (pintype "passive"))
      (node (ref "C_H21-") (pin "2") (pinfunction "2_2") (pintype "passive"))
      (node (ref "C_H22-") (pin "2") (pinfunction "2_2") (pintype "passive"))
      (node (ref "C_N11-") (pin "2") (pinfunction "2_2") (pintype "passive"))
      (node (ref "C_N12-") (pin "2") (pinfunction "2_2") (pintype "passive"))
      (node (ref "C_N21-") (pin "2") (pinfunction "2_2") (pintype "passive"))
      (node (ref "C_N22-") (pin "2") (pinfunction "2_2") (pintype "passive"))
      (node (ref "C_T11-") (pin "2") (pinfunction "2_2") (pintype "passive"))
      (node (ref "C_T12-") (pin "2") (pinfunction "2_2") (pintype "passive"))
      (node (ref "C_T21-") (pin "2") (pinfunction "2_2") (pintype "passive"))
      (node (ref "C_T22-") (pin "2") (pinfunction "2_2") (pintype "passive"))
      (node (ref "H11") (pin "4") (pinfunction "V-_4") (pintype "power_in"))
      (node (ref "H12") (pin "4") (pinfunction "V-_4") (pintype "power_in"))
      (node (ref "H21") (pin "4") (pinfunction "V-_4") (pintype "power_in"))
      (node (ref "H22") (pin "4") (pinfunction "V-_4") (pintype "power_in"))
      (node (ref "JP7") (pin "4") (pinfunction "4_4") (pintype "passive"))
      (node (ref "N11") (pin "4") (pinfunction "V-_4") (pintype "power_in"))
      (node (ref "N12") (pin "4") (pinfunction "V-_4") (pintype "power_in"))
      (node (ref "N21") (pin "4") (pinfunction "V-_4") (pintype "power_in"))
      (node (ref "N22") (pin "4") (pinfunction "V-_4") (pintype "power_in"))
      (node (ref "T11") (pin "4") (pinfunction "V-_4") (pintype "power_in"))
      (node (ref "T12") (pin "4") (pinfunction "V-_4") (pintype "power_in"))
      (node (ref "T21") (pin "4") (pinfunction "V-_4") (pintype "power_in"))
      (node (ref "T22") (pin "4") (pinfunction "V-_4") (pintype "power_in"))
    )
    (net (code "5") (name "-9V") (class "Default")
      (node (ref "C_-9") (pin "-") (pinfunction "-_-") (pintype "passive"))
      (node (ref "C_INA1-") (pin "1") (pinfunction "1_1") (pintype "passive"))
      (node (ref "C_INA2-") (pin "1") (pinfunction "1_1") (pintype "passive"))
      (node (ref "INA_1") (pin "4") (pinfunction "-VS_4") (pintype "bidirectional"))
      (node (ref "INA_2") (pin "4") (pinfunction "-VS_4") (pintype "bidirectional"))
      (node (ref "JP7") (pin "1") (pinfunction "1_1") (pintype "passive"))
    )
    (net (code "6") (name "ACLK") (class "Default")
      (node (ref "CLOCK") (pin "3") (pinfunction "3_3") (pintype "passive"))
      (node (ref "U$1") (pin "35") (pinfunction "P1.2_35") (pintype "bidirectional"))
    )
    (net (code "7") (name "ACT_LED") (class "Default")
      (node (ref "LED_ACT") (pin "K") (pinfunction "C_K") (pintype "passive"))
      (node (ref "U$1") (pin "93") (pinfunction "P8.0_93") (pintype "bidirectional"))
    )
    (net (code "8") (name "AGND") (class "Default")
      (node (ref "C+1.5") (pin "-") (pinfunction "-_-") (pintype "passive"))
      (node (ref "C+9") (pin "-") (pinfunction "-_-") (pintype "passive"))
      (node (ref "C-1.5") (pin "+") (pinfunction "+_+") (pintype "passive"))
      (node (ref "C22") (pin "2") (pinfunction "2_2") (pintype "passive"))
      (node (ref "C23") (pin "2") (pinfunction "2_2") (pintype "passive"))
      (node (ref "C28") (pin "2") (pinfunction "2_2") (pintype "passive"))
      (node (ref "C29") (pin "2") (pinfunction "2_2") (pintype "passive"))
      (node (ref "C30") (pin "2") (pinfunction "2_2") (pintype "passive"))
      (node (ref "C31") (pin "2") (pinfunction "2_2") (pintype "passive"))
      (node (ref "C32") (pin "2") (pinfunction "2_2") (pintype "passive"))
      (node (ref "C_-9") (pin "+") (pinfunction "+_+") (pintype "passive"))
      (node (ref "C_H11+") (pin "2") (pinfunction "2_2") (pintype "passive"))
      (node (ref "C_H11-") (pin "1") (pinfunction "1_1") (pintype "passive"))
      (node (ref "C_H12+") (pin "2") (pinfunction "2_2") (pintype "passive"))
      (node (ref "C_H12-") (pin "1") (pinfunction "1_1") (pintype "passive"))
      (node (ref "C_H21+") (pin "2") (pinfunction "2_2") (pintype "passive"))
      (node (ref "C_H21-") (pin "1") (pinfunction "1_1") (pintype "passive"))
      (node (ref "C_H22+") (pin "2") (pinfunction "2_2") (pintype "passive"))
      (node (ref "C_H22-") (pin "1") (pinfunction "1_1") (pintype "passive"))
      (node (ref "C_INA1+") (pin "2") (pinfunction "2_2") (pintype "passive"))
      (node (ref "C_INA1-") (pin "2") (pinfunction "2_2") (pintype "passive"))
      (node (ref "C_INA2+") (pin "2") (pinfunction "2_2") (pintype "passive"))
      (node (ref "C_INA2-") (pin "2") (pinfunction "2_2") (pintype "passive"))
      (node (ref "C_N11+") (pin "2") (pinfunction "2_2") (pintype "passive"))
      (node (ref "C_N11-") (pin "1") (pinfunction "1_1") (pintype "passive"))
      (node (ref "C_N12+") (pin "2") (pinfunction "2_2") (pintype "passive"))
      (node (ref "C_N12-") (pin "1") (pinfunction "1_1") (pintype "passive"))
      (node (ref "C_N21+") (pin "2") (pinfunction "2_2") (pintype "passive"))
      (node (ref "C_N21-") (pin "1") (pinfunction "1_1") (pintype "passive"))
      (node (ref "C_N22+") (pin "2") (pinfunction "2_2") (pintype "passive"))
      (node (ref "C_N22-") (pin "1") (pinfunction "1_1") (pintype "passive"))
      (node (ref "C_T11+") (pin "2") (pinfunction "2_2") (pintype "passive"))
      (node (ref "C_T11-") (pin "1") (pinfunction "1_1") (pintype "passive"))
      (node (ref "C_T11.2") (pin "1") (pinfunction "1_1") (pintype "passive"))
      (node (ref "C_T12+") (pin "2") (pinfunction "2_2") (pintype "passive"))
      (node (ref "C_T12-") (pin "1") (pinfunction "1_1") (pintype "passive"))
      (node (ref "C_T12.2") (pin "1") (pinfunction "1_1") (pintype "passive"))
      (node (ref "C_T21+") (pin "2") (pinfunction "2_2") (pintype "passive"))
      (node (ref "C_T21-") (pin "1") (pinfunction "1_1") (pintype "passive"))
      (node (ref "C_T21.2") (pin "1") (pinfunction "1_1") (pintype "passive"))
      (node (ref "C_T22+") (pin "2") (pinfunction "2_2") (pintype "passive"))
      (node (ref "C_T22-") (pin "1") (pinfunction "1_1") (pintype "passive"))
      (node (ref "C_T22.2") (pin "1") (pinfunction "1_1") (pintype "passive"))
      (node (ref "D_Z1.2") (pin "1") (pinfunction "A_1") (pintype "passive"))
      (node (ref "D_Z2.2") (pin "1") (pinfunction "A_1") (pintype "passive"))
      (node (ref "JP7") (pin "2") (pinfunction "2_2") (pintype "passive"))
      (node (ref "JP7") (pin "5") (pinfunction "5_5") (pintype "passive"))
      (node (ref "R2") (pin "2") (pinfunction "2_2") (pintype "passive"))
      (node (ref "R_H11.2") (pin "1") (pinfunction "1_1") (pintype "passive"))
      (node (ref "R_H12.2") (pin "1") (pinfunction "1_1") (pintype "passive"))
      (node (ref "R_H21.2") (pin "1") (pinfunction "1_1") (pintype "passive"))
      (node (ref "R_H22.2") (pin "1") (pinfunction "1_1") (pintype "passive"))
      (node (ref "R_N1.2") (pin "1") (pinfunction "1_1") (pintype "passive"))
      (node (ref "R_N2.2") (pin "1") (pinfunction "1_1") (pintype "passive"))
      (node (ref "U$1") (pin "10") (pinfunction "AVSS2_10") (pintype "bidirectional"))
      (node (ref "U$1") (pin "13") (pinfunction "SD4N0_13") (pintype "bidirectional"))
      (node (ref "U$1") (pin "18") (pinfunction "AVSS1_18") (pintype "bidirectional"))
      (node (ref "U$1") (pin "2") (pinfunction "SD0N0_2") (pintype "bidirectional"))
    )
    (net (code "9") (name "AUXVCC1") (class "Default")
      (node (ref "C26") (pin "1") (pinfunction "1_1") (pintype "passive"))
      (node (ref "C27") (pin "1") (pinfunction "1_1") (pintype "passive"))
      (node (ref "U$1") (pin "22") (pinfunction "AUXVCC1_22") (pintype "bidirectional"))
    )
    (net (code "10") (name "AUXVCC2") (class "Default")
      (node (ref "C24") (pin "1") (pinfunction "1_1") (pintype "passive"))
      (node (ref "C25") (pin "1") (pinfunction "1_1") (pintype "passive"))
      (node (ref "U$1") (pin "21") (pinfunction "AUXVCC2_21") (pintype "bidirectional"))
    )
    (net (code "11") (name "AUXVCC3") (class "Default")
      (node (ref "C43") (pin "1") (pinfunction "1_1") (pintype "passive"))
      (node (ref "C44") (pin "1") (pinfunction "1_1") (pintype "passive"))
      (node (ref "U$1") (pin "29") (pinfunction "AUXVCC3_29") (pintype "bidirectional"))
    )
    (net (code "12") (name "AVCC") (class "Default")
      (node (ref "C29") (pin "1") (pinfunction "1_1") (pintype "passive"))
      (node (ref "C31") (pin "1") (pinfunction "1_1") (pintype "passive"))
      (node (ref "R1") (pin "2") (pinfunction "2_2") (pintype "passive"))
      (node (ref "U$1") (pin "19") (pinfunction "AVCC_19") (pintype "bidirectional"))
    )
    (net (code "13") (name "BTN1") (class "Default")
      (node (ref "BTN_1") (pin "2") (pinfunction "S_2") (pintype "passive"))
      (node (ref "R120") (pin "2") (pinfunction "2_2") (pintype "passive"))
      (node (ref "U$1") (pin "91") (pinfunction "P7.6_91") (pintype "bidirectional"))
    )
    (net (code "14") (name "BTN2") (class "Default")
      (node (ref "BTN_2") (pin "2") (pinfunction "S_2") (pintype "passive"))
      (node (ref "R121") (pin "2") (pinfunction "2_2") (pintype "passive"))
      (node (ref "U$1") (pin "92") (pinfunction "P7.7_92") (pintype "bidirectional"))
    )
    (net (code "15") (name "BTN3") (class "Default")
      (node (ref "U$1") (pin "83") (pinfunction "P6.6_83") (pintype "bidirectional"))
    )
    (net (code "16") (name "BTN4") (class "Default")
      (node (ref "BTN_4") (pin "2") (pinfunction "S_2") (pintype "passive"))
      (node (ref "R123") (pin "2") (pinfunction "2_2") (pintype "passive"))
      (node (ref "U$1") (pin "84") (pinfunction "P6.7_84") (pintype "bidirectional"))
    )
    (net (code "17") (name "DGND") (class "Default")
      (node (ref "BTN_1") (pin "1") (pinfunction "P_1") (pintype "passive"))
      (node (ref "BTN_2") (pin "1") (pinfunction "P_1") (pintype "passive"))
      (node (ref "BTN_3") (pin "1") (pinfunction "P_1") (pintype "passive"))
      (node (ref "BTN_4") (pin "1") (pinfunction "P_1") (pintype "passive"))
      (node (ref "C+3") (pin "-") (pinfunction "-_-") (pintype "passive"))
      (node (ref "C100") (pin "2") (pinfunction "2_2") (pintype "passive"))
      (node (ref "C101") (pin "2") (pinfunction "2_2") (pintype "passive"))
      (node (ref "C110") (pin "1") (pinfunction "1_1") (pintype "passive"))
      (node (ref "C24") (pin "2") (pinfunction "2_2") (pintype "passive"))
      (node (ref "C25") (pin "2") (pinfunction "2_2") (pintype "passive"))
      (node (ref "C26") (pin "2") (pinfunction "2_2") (pintype "passive"))
      (node (ref "C27") (pin "2") (pinfunction "2_2") (pintype "passive"))
      (node (ref "C33") (pin "2") (pinfunction "2_2") (pintype "passive"))
      (node (ref "C34") (pin "2") (pinfunction "2_2") (pintype "passive"))
      (node (ref "C35") (pin "2") (pinfunction "2_2") (pintype "passive"))
      (node (ref "C36") (pin "2") (pinfunction "2_2") (pintype "passive"))
      (node (ref "C38") (pin "2") (pinfunction "2_2") (pintype "passive"))
      (node (ref "C43") (pin "2") (pinfunction "2_2") (pintype "passive"))
      (node (ref "C44") (pin "2") (pinfunction "2_2") (pintype "passive"))
      (node (ref "CLOCK") (pin "1") (pinfunction "1_1") (pintype "passive"))
      (node (ref "DGND1") (pin "1") (pinfunction "1_1") (pintype "passive"))
      (node (ref "DGND2") (pin "1") (pinfunction "1_1") (pintype "passive"))
      (node (ref "JP7") (pin "7") (pinfunction "7_7") (pintype "passive"))
      (node (ref "JTAG") (pin "9") (pinfunction "9_9") (pintype "passive"))
      (node (ref "R2") (pin "1") (pinfunction "1_1") (pintype "passive"))
      (node (ref "RESET") (pin "2") (pinfunction "S_2") (pintype "passive"))
      (node (ref "U$1") (pin "14") (pinfunction "SD5P0_14") (pintype "bidirectional"))
      (node (ref "U$1") (pin "15") (pinfunction "SD5N0_15") (pintype "bidirectional"))
      (node (ref "U$1") (pin "16") (pinfunction "SD6P0_16") (pintype "bidirectional"))
      (node (ref "U$1") (pin "17") (pinfunction "SD6N0_17") (pintype "bidirectional"))
      (node (ref "U$1") (pin "25") (pinfunction "DVSS1_25") (pintype "bidirectional"))
      (node (ref "U$1") (pin "3") (pinfunction "SD1P0_3") (pintype "bidirectional"))
      (node (ref "U$1") (pin "38") (pinfunction "COM0_38") (pintype "bidirectional"))
      (node (ref "U$1") (pin "39") (pinfunction "COM1_39") (pintype "bidirectional"))
      (node (ref "U$1") (pin "4") (pinfunction "SD1N0_4") (pintype "bidirectional"))
      (node (ref "U$1") (pin "46") (pinfunction "LCDCAP_46") (pintype "bidirectional"))
      (node (ref "U$1") (pin "5") (pinfunction "SD2P0_5") (pintype "bidirectional"))
      (node (ref "U$1") (pin "6") (pinfunction "SD2N0_6") (pintype "bidirectional"))
      (node (ref "U$1") (pin "7") (pinfunction "SD3P0_7") (pintype "bidirectional"))
      (node (ref "U$1") (pin "76") (pinfunction "DVSS2_76") (pintype "bidirectional"))
      (node (ref "U$1") (pin "8") (pinfunction "SD3N0_8") (pintype "bidirectional"))
      (node (ref "XT1") (pin "P3") (pinfunction "3_P3") (pintype "bidirectional"))
    )
    (net (code "18") (name "DVCC") (class "Default")
      (node (ref "C33") (pin "1") (pinfunction "1_1") (pintype "passive"))
      (node (ref "C35") (pin "1") (pinfunction "1_1") (pintype "passive"))
      (node (ref "JP14") (pin "2") (pinfunction "2_2") (pintype "passive"))
      (node (ref "R1") (pin "1") (pinfunction "1_1") (pintype "passive"))
      (node (ref "R101") (pin "1") (pinfunction "1_1") (pintype "passive"))
      (node (ref "R110") (pin "1") (pinfunction "1_1") (pintype "passive"))
      (node (ref "R111") (pin "1") (pinfunction "1_1") (pintype "passive"))
      (node (ref "R112") (pin "1") (pinfunction "1_1") (pintype "passive"))
      (node (ref "R114") (pin "1") (pinfunction "1_1") (pintype "passive"))
      (node (ref "R115") (pin "1") (pinfunction "1_1") (pintype "passive"))
      (node (ref "R116") (pin "1") (pinfunction "1_1") (pintype "passive"))
      (node (ref "R117") (pin "1") (pinfunction "1_1") (pintype "passive"))
      (node (ref "R120") (pin "1") (pinfunction "1_1") (pintype "passive"))
      (node (ref "R121") (pin "1") (pinfunction "1_1") (pintype "passive"))
      (node (ref "R122") (pin "1") (pinfunction "1_1") (pintype "passive"))
      (node (ref "R123") (pin "1") (pinfunction "1_1") (pintype "passive"))
      (node (ref "U$1") (pin "24") (pinfunction "DVCC_24") (pintype "bidirectional"))
    )
    (net (code "19") (name "DVSYS") (class "Default")
      (node (ref "C34") (pin "1") (pinfunction "1_1") (pintype "passive"))
      (node (ref "C36") (pin "1") (pinfunction "1_1") (pintype "passive"))
      (node (ref "U$1") (pin "23") (pinfunction "VDSYS1_23") (pintype "bidirectional"))
      (node (ref "U$1") (pin "75") (pinfunction "VDSYS2_75") (pintype "bidirectional"))
    )
    (net (code "20") (name "EXT") (class "Default")
      (node (ref "JP14") (pin "3") (pinfunction "3_3") (pintype "passive"))
      (node (ref "JTAG") (pin "4") (pinfunction "4_4") (pintype "passive"))
    )
    (net (code "21") (name "H1_OUT") (class "Default")
      (node (ref "C_H12.0") (pin "1") (pinfunction "1_1") (pintype "passive"))
      (node (ref "H12") (pin "6") (pinfunction "OUT_6") (pintype "output"))
      (node (ref "JP9") (pin "2") (pinfunction "2_2") (pintype "passive"))
      (node (ref "JP9") (pin "4") (pinfunction "4_4") (pintype "passive"))
      (node (ref "JP9") (pin "6") (pinfunction "6_6") (pintype "passive"))
      (node (ref "TP2") (pin "TP") (pinfunction "TP_TP") (pintype "input"))
    )
    (net (code "22") (name "H2_OUT") (class "Default")
      (node (ref "C_H22.0") (pin "1") (pinfunction "1_1") (pintype "passive"))
      (node (ref "H22") (pin "6") (pinfunction "OUT_6") (pintype "output"))
      (node (ref "JP3") (pin "2") (pinfunction "2_2") (pintype "passive"))
      (node (ref "JP3") (pin "4") (pinfunction "4_4") (pintype "passive"))
      (node (ref "JP3") (pin "6") (pinfunction "6_6") (pintype "passive"))
      (node (ref "TP9") (pin "TP") (pinfunction "TP_TP") (pintype "input"))
    )
    (net (code "23") (name "H11_OUT") (class "Default")
      (node (ref "C_H11.0") (pin "1") (pinfunction "1_1") (pintype "passive"))
      (node (ref "C_H12.1") (pin "1") (pinfunction "1_1") (pintype "passive"))
      (node (ref "H11") (pin "6") (pinfunction "OUT_6") (pintype "output"))
      (node (ref "TP15") (pin "TP") (pinfunction "TP_TP") (pintype "input"))
    )
    (net (code "24") (name "H21_OUT") (class "Default")
      (node (ref "C_H21.0") (pin "1") (pinfunction "1_1") (pintype "passive"))
      (node (ref "C_H22.1") (pin "1") (pinfunction "1_1") (pintype "passive"))
      (node (ref "H21") (pin "6") (pinfunction "OUT_6") (pintype "output"))
      (node (ref "TP17") (pin "TP") (pinfunction "TP_TP") (pintype "input"))
    )
    (net (code "25") (name "INA1_OUT") (class "Default")
      (node (ref "INA_1") (pin "6") (pinfunction "OUT_6") (pintype "bidirectional"))
      (node (ref "JP8") (pin "2") (pinfunction "2_2") (pintype "passive"))
      (node (ref "JP8") (pin "4") (pinfunction "4_4") (pintype "passive"))
      (node (ref "JP8") (pin "6") (pinfunction "6_6") (pintype "passive"))
      (node (ref "RZ_1") (pin "2") (pinfunction "2_2") (pintype "passive"))
      (node (ref "TP1") (pin "TP") (pinfunction "TP_TP") (pintype "input"))
    )
    (net (code "26") (name "INA2_OUT") (class "Default")
      (node (ref "INA_2") (pin "6") (pinfunction "OUT_6") (pintype "bidirectional"))
      (node (ref "JP2") (pin "2") (pinfunction "2_2") (pintype "passive"))
      (node (ref "JP2") (pin "4") (pinfunction "4_4") (pintype "passive"))
      (node (ref "JP2") (pin "6") (pinfunction "6_6") (pintype "passive"))
      (node (ref "RZ_2") (pin "2") (pinfunction "2_2") (pintype "passive"))
      (node (ref "TP8") (pin "TP") (pinfunction "TP_TP") (pintype "input"))
    )
    (net (code "27") (name "INT") (class "Default")
      (node (ref "JP14") (pin "1") (pinfunction "1_1") (pintype "passive"))
      (node (ref "JTAG") (pin "2") (pinfunction "2_2") (pintype "passive"))
    )
    (net (code "28") (name "LED1") (class "Default")
      (node (ref "LED3") (pin "K") (pinfunction "C_K") (pintype "passive"))
      (node (ref "U$1") (pin "85") (pinfunction "P7.0_85") (pintype "bidirectional"))
    )
    (net (code "29") (name "LED2") (class "Default")
      (node (ref "LED2") (pin "K") (pinfunction "C_K") (pintype "passive"))
      (node (ref "U$1") (pin "86") (pinfunction "P7.1_86") (pintype "bidirectional"))
    )
    (net (code "30") (name "LED3") (class "Default")
      (node (ref "LED1") (pin "K") (pinfunction "C_K") (pintype "passive"))
      (node (ref "U$1") (pin "87") (pinfunction "P7.2_87") (pintype "bidirectional"))
    )
    (net (code "31") (name "LED4") (class "Default")
      (node (ref "LED4") (pin "K") (pinfunction "C_K") (pintype "passive"))
      (node (ref "U$1") (pin "88") (pinfunction "P7.3_88") (pintype "bidirectional"))
    )
    (net (code "32") (name "LED5") (class "Default")
      (node (ref "LED5") (pin "K") (pinfunction "C_K") (pintype "passive"))
      (node (ref "U$1") (pin "89") (pinfunction "P7.4_89") (pintype "bidirectional"))
    )
    (net (code "33") (name "LED6") (class "Default")
      (node (ref "LED6") (pin "K") (pinfunction "C_K") (pintype "passive"))
      (node (ref "U$1") (pin "90") (pinfunction "P7.5_90") (pintype "bidirectional"))
    )
    (net (code "34") (name "LS+") (class "Default")
      (node (ref "INA_2") (pin "3") (pinfunction "+IN_3") (pintype "bidirectional"))
      (node (ref "J2") (pin "4") (pinfunction "4_4") (pintype "passive"))
      (node (ref "R_LS1") (pin "1") (pinfunction "1_1") (pintype "passive"))
    )
    (net (code "35") (name "LS-") (class "Default")
      (node (ref "INA_2") (pin "2") (pinfunction "-IN_2") (pintype "bidirectional"))
      (node (ref "J2") (pin "1") (pinfunction "1_1") (pintype "passive"))
      (node (ref "R_LS1") (pin "2") (pinfunction "2_2") (pintype "passive"))
    )
    (net (code "36") (name "LS_TO_ADC2") (class "Default")
      (node (ref "JP16") (pin "2") (pinfunction "2_2") (pintype "passive"))
      (node (ref "JP3") (pin "5") (pinfunction "5_5") (pintype "passive"))
      (node (ref "JP4") (pin "3") (pinfunction "3_3") (pintype "passive"))
      (node (ref "JP6") (pin "1") (pinfunction "1_1") (pintype "passive"))
      (node (ref "TP12_H2") (pin "TP") (pinfunction "TP_TP") (pintype "input"))
      (node (ref "TP13_T2") (pin "TP") (pinfunction "TP_TP") (pintype "input"))
      (node (ref "TP14_N2") (pin "TP") (pinfunction "TP_TP") (pintype "input"))
    )
    (net (code "37") (name "MCLK") (class "Default")
      (node (ref "CLOCK") (pin "4") (pinfunction "4_4") (pintype "passive"))
      (node (ref "U$1") (pin "33") (pinfunction "P1.4_33") (pintype "bidirectional"))
    )
    (net (code "38") (name "N1_OUT") (class "Default")
      (node (ref "C_N11.0") (pin "1") (pinfunction "1_1") (pintype "passive"))
      (node (ref "JP11") (pin "2") (pinfunction "2_2") (pintype "passive"))
      (node (ref "JP11") (pin "4") (pinfunction "4_4") (pintype "passive"))
      (node (ref "JP11") (pin "6") (pinfunction "6_6") (pintype "passive"))
      (node (ref "N11") (pin "6") (pinfunction "OUT_6") (pintype "output"))
      (node (ref "R_N1.5") (pin "2") (pinfunction "2_2") (pintype "passive"))
      (node (ref "TP4") (pin "TP") (pinfunction "TP_TP") (pintype "input"))
    )
    (net (code "39") (name "N2_OUT") (class "Default")
      (node (ref "C_N21.0") (pin "1") (pinfunction "1_1") (pintype "passive"))
      (node (ref "JP6") (pin "2") (pinfunction "2_2") (pintype "passive"))
      (node (ref "JP6") (pin "4") (pinfunction "4_4") (pintype "passive"))
      (node (ref "JP6") (pin "6") (pinfunction "6_6") (pintype "passive"))
      (node (ref "N21") (pin "6") (pinfunction "OUT_6") (pintype "output"))
      (node (ref "R_N2.5") (pin "2") (pinfunction "2_2") (pintype "passive"))
      (node (ref "TP11") (pin "TP") (pinfunction "TP_TP") (pintype "input"))
    )
    (net (code "40") (name "Net-(C_H11.1-Pad1)") (class "Default")
      (node (ref "C_H11.1") (pin "1") (pinfunction "1_1") (pintype "passive"))
      (node (ref "JP10") (pin "5") (pinfunction "5_5") (pintype "passive"))
      (node (ref "JP11") (pin "5") (pinfunction "5_5") (pintype "passive"))
      (node (ref "JP8") (pin "5") (pinfunction "5_5") (pintype "passive"))
    )
    (net (code "41") (name "Net-(C_H11.1-Pad2)") (class "Default")
      (node (ref "C_H11.1") (pin "2") (pinfunction "2_2") (pintype "passive"))
      (node (ref "C_H11.2") (pin "1") (pinfunction "1_1") (pintype "passive"))
      (node (ref "R_H11.1") (pin "1") (pinfunction "1_1") (pintype "passive"))
    )
    (net (code "42") (name "Net-(C_H12.1-Pad2)") (class "Default")
      (node (ref "C_H12.1") (pin "2") (pinfunction "2_2") (pintype "passive"))
      (node (ref "C_H12.2") (pin "1") (pinfunction "1_1") (pintype "passive"))
      (node (ref "R_H12.1") (pin "1") (pinfunction "1_1") (pintype "passive"))
    )
    (net (code "43") (name "Net-(C_H21.1-Pad1)") (class "Default")
      (node (ref "C_H21.1") (pin "1") (pinfunction "1_1") (pintype "passive"))
      (node (ref "JP2") (pin "5") (pinfunction "5_5") (pintype "passive"))
      (node (ref "JP4") (pin "5") (pinfunction "5_5") (pintype "passive"))
      (node (ref "JP6") (pin "5") (pinfunction "5_5") (pintype "passive"))
    )
    (net (code "44") (name "Net-(C_H21.1-Pad2)") (class "Default")
      (node (ref "C_H21.1") (pin "2") (pinfunction "2_2") (pintype "passive"))
      (node (ref "C_H21.2") (pin "1") (pinfunction "1_1") (pintype "passive"))
      (node (ref "R_H21.1") (pin "1") (pinfunction "1_1") (pintype "passive"))
    )
    (net (code "45") (name "Net-(C_H22.1-Pad2)") (class "Default")
      (node (ref "C_H22.1") (pin "2") (pinfunction "2_2") (pintype "passive"))
      (node (ref "C_H22.2") (pin "1") (pinfunction "1_1") (pintype "passive"))
      (node (ref "R_H22.1") (pin "1") (pinfunction "1_1") (pintype "passive"))
    )
    (net (code "46") (name "Net-(C_N1.1-Pad1)") (class "Default")
      (node (ref "C_N1.1") (pin "1") (pinfunction "1_1") (pintype "passive"))
      (node (ref "JP10") (pin "1") (pinfunction "1_1") (pintype "passive"))
      (node (ref "JP8") (pin "1") (pinfunction "1_1") (pintype "passive"))
      (node (ref "JP9") (pin "1") (pinfunction "1_1") (pintype "passive"))
      (node (ref "R_N1.1") (pin "1") (pinfunction "1_1") (pintype "passive"))
      (node (ref "R_N1.6") (pin "1") (pinfunction "1_1") (pintype "passive"))
    )
    (net (code "47") (name "Net-(C_N2.1-Pad1)") (class "Default")
      (node (ref "C_N2.1") (pin "1") (pinfunction "1_1") (pintype "passive"))
      (node (ref "JP2") (pin "1") (pinfunction "1_1") (pintype "passive"))
      (node (ref "JP3") (pin "1") (pinfunction "1_1") (pintype "passive"))
      (node (ref "JP4") (pin "1") (pinfunction "1_1") (pintype "passive"))
      (node (ref "R_N2.1") (pin "1") (pinfunction "1_1") (pintype "passive"))
      (node (ref "R_N2.6") (pin "1") (pinfunction "1_1") (pintype "passive"))
    )
    (net (code "48") (name "Net-(C_T11.1-Pad1)") (class "Default")
      (node (ref "C_T11.1") (pin "1") (pinfunction "1_1") (pintype "passive"))
      (node (ref "R_T11.1") (pin "2") (pinfunction "2_2") (pintype "passive"))
      (node (ref "R_T11.2") (pin "1") (pinfunction "1_1") (pintype "passive"))
    )
    (net (code "49") (name "Net-(C_T12.1-Pad1)") (class "Default")
      (node (ref "C_T12.1") (pin "1") (pinfunction "1_1") (pintype "passive"))
      (node (ref "R_T12.1") (pin "2") (pinfunction "2_2") (pintype "passive"))
      (node (ref "R_T12.2") (pin "1") (pinfunction "1_1") (pintype "passive"))
    )
    (net (code "50") (name "Net-(C_T21.1-Pad1)") (class "Default")
      (node (ref "C_T21.1") (pin "1") (pinfunction "1_1") (pintype "passive"))
      (node (ref "R_T21.1") (pin "2") (pinfunction "2_2") (pintype "passive"))
      (node (ref "R_T21.2") (pin "1") (pinfunction "1_1") (pintype "passive"))
    )
    (net (code "51") (name "Net-(C_T22.1-Pad1)") (class "Default")
      (node (ref "C_T22.1") (pin "1") (pinfunction "1_1") (pintype "passive"))
      (node (ref "R_T22.1") (pin "2") (pinfunction "2_2") (pintype "passive"))
      (node (ref "R_T22.2") (pin "1") (pinfunction "1_1") (pintype "passive"))
    )
    (net (code "52") (name "Net-(D_Z1.1-A)") (class "Default")
      (node (ref "D_Z1.1") (pin "1") (pinfunction "A_1") (pintype "passive"))
      (node (ref "RZ_1") (pin "1") (pinfunction "1_1") (pintype "passive"))
    )
    (net (code "53") (name "Net-(D_Z1.1-C)") (class "Default")
      (node (ref "D_Z1.1") (pin "2") (pinfunction "C_2") (pintype "passive"))
      (node (ref "D_Z1.2") (pin "2") (pinfunction "C_2") (pintype "passive"))
    )
    (net (code "54") (name "Net-(D_Z2.1-A)") (class "Default")
      (node (ref "D_Z2.1") (pin "1") (pinfunction "A_1") (pintype "passive"))
      (node (ref "RZ_2") (pin "1") (pinfunction "1_1") (pintype "passive"))
    )
    (net (code "55") (name "Net-(D_Z2.1-C)") (class "Default")
      (node (ref "D_Z2.1") (pin "2") (pinfunction "C_2") (pintype "passive"))
      (node (ref "D_Z2.2") (pin "2") (pinfunction "C_2") (pintype "passive"))
    )
    (net (code "56") (name "Net-(H11-IN+)") (class "Default")
      (node (ref "C_H11.2") (pin "2") (pinfunction "2_2") (pintype "passive"))
      (node (ref "H11") (pin "3") (pinfunction "IN+_3") (pintype "input"))
      (node (ref "R_H11.2") (pin "2") (pinfunction "2_2") (pintype "passive"))
    )
    (net (code "57") (name "Net-(H11-IN-)") (class "Default")
      (node (ref "C_H11.0") (pin "2") (pinfunction "2_2") (pintype "passive"))
      (node (ref "H11") (pin "2") (pinfunction "IN-_2") (pintype "input"))
      (node (ref "R_H11.1") (pin "2") (pinfunction "2_2") (pintype "passive"))
    )
    (net (code "58") (name "Net-(H12-IN+)") (class "Default")
      (node (ref "C_H12.2") (pin "2") (pinfunction "2_2") (pintype "passive"))
      (node (ref "H12") (pin "3") (pinfunction "IN+_3") (pintype "input"))
      (node (ref "R_H12.2") (pin "2") (pinfunction "2_2") (pintype "passive"))
    )
    (net (code "59") (name "Net-(H12-IN-)") (class "Default")
      (node (ref "C_H12.0") (pin "2") (pinfunction "2_2") (pintype "passive"))
      (node (ref "H12") (pin "2") (pinfunction "IN-_2") (pintype "input"))
      (node (ref "R_H12.1") (pin "2") (pinfunction "2_2") (pintype "passive"))
    )
    (net (code "60") (name "Net-(H21-IN+)") (class "Default")
      (node (ref "C_H21.2") (pin "2") (pinfunction "2_2") (pintype "passive"))
      (node (ref "H21") (pin "3") (pinfunction "IN+_3") (pintype "input"))
      (node (ref "R_H21.2") (pin "2") (pinfunction "2_2") (pintype "passive"))
    )
    (net (code "61") (name "Net-(H21-IN-)") (class "Default")
      (node (ref "C_H21.0") (pin "2") (pinfunction "2_2") (pintype "passive"))
      (node (ref "H21") (pin "2") (pinfunction "IN-_2") (pintype "input"))
      (node (ref "R_H21.1") (pin "2") (pinfunction "2_2") (pintype "passive"))
    )
    (net (code "62") (name "Net-(H22-IN+)") (class "Default")
      (node (ref "C_H22.2") (pin "2") (pinfunction "2_2") (pintype "passive"))
      (node (ref "H22") (pin "3") (pinfunction "IN+_3") (pintype "input"))
      (node (ref "R_H22.2") (pin "2") (pinfunction "2_2") (pintype "passive"))
    )
    (net (code "63") (name "Net-(H22-IN-)") (class "Default")
      (node (ref "C_H22.0") (pin "2") (pinfunction "2_2") (pintype "passive"))
      (node (ref "H22") (pin "2") (pinfunction "IN-_2") (pintype "input"))
      (node (ref "R_H22.1") (pin "2") (pinfunction "2_2") (pintype "passive"))
    )
    (net (code "64") (name "Net-(INA_1-RG-Pad1)") (class "Default")
      (node (ref "INA_1") (pin "1") (pinfunction "RG_1") (pintype "bidirectional"))
      (node (ref "JP5") (pin "1") (pinfunction "1_1") (pintype "passive"))
      (node (ref "JP5") (pin "3") (pinfunction "3_3") (pintype "passive"))
    )
    (net (code "65") (name "Net-(INA_1-RG-Pad8)") (class "Default")
      (node (ref "INA_1") (pin "8") (pinfunction "RG_8") (pintype "bidirectional"))
      (node (ref "R_INA1_CONST") (pin "2") (pinfunction "2_2") (pintype "passive"))
      (node (ref "R_INA1_MIN") (pin "2") (pinfunction "2_2") (pintype "passive"))
    )
    (net (code "66") (name "Net-(INA_2-RG-Pad1)") (class "Default")
      (node (ref "INA_2") (pin "1") (pinfunction "RG_1") (pintype "bidirectional"))
      (node (ref "JP1") (pin "1") (pinfunction "1_1") (pintype "passive"))
      (node (ref "JP1") (pin "3") (pinfunction "3_3") (pintype "passive"))
    )
    (net (code "67") (name "Net-(INA_2-RG-Pad8)") (class "Default")
      (node (ref "INA_2") (pin "8") (pinfunction "RG_8") (pintype "bidirectional"))
      (node (ref "R_INA2_CONST") (pin "2") (pinfunction "2_2") (pintype "passive"))
      (node (ref "R_INA2_MIN") (pin "2") (pinfunction "2_2") (pintype "passive"))
    )
    (net (code "68") (name "Net-(J1-Pad5)") (class "Default")
      (node (ref "J1") (pin "5") (pinfunction "5_5") (pintype "passive"))
      (node (ref "JP13") (pin "2") (pinfunction "2_2") (pintype "passive"))
    )
    (net (code "69") (name "Net-(J2-Pad5)") (class "Default")
      (node (ref "J2") (pin "5") (pinfunction "5_5") (pintype "passive"))
      (node (ref "JP12") (pin "2") (pinfunction "2_2") (pintype "passive"))
    )
    (net (code "70") (name "Net-(JP1-Pad4)") (class "Default")
      (node (ref "JP1") (pin "4") (pinfunction "4_4") (pintype "passive"))
      (node (ref "R_INA2_CONST") (pin "1") (pinfunction "1_1") (pintype "passive"))
    )
    (net (code "71") (name "Net-(JP2-Pad3)") (class "Default")
      (node (ref "JP2") (pin "3") (pinfunction "3_3") (pintype "passive"))
      (node (ref "JP3") (pin "3") (pinfunction "3_3") (pintype "passive"))
      (node (ref "JP6") (pin "3") (pinfunction "3_3") (pintype "passive"))
      (node (ref "R_T21.1") (pin "1") (pinfunction "1_1") (pintype "passive"))
    )
    (net (code "72") (name "Net-(JP5-Pad4)") (class "Default")
      (node (ref "JP5") (pin "4") (pinfunction "4_4") (pintype "passive"))
      (node (ref "R_INA1_CONST") (pin "1") (pinfunction "1_1") (pintype "passive"))
    )
    (net (code "73") (name "Net-(JP11-Pad3)") (class "Default")
      (node (ref "JP11") (pin "3") (pinfunction "3_3") (pintype "passive"))
      (node (ref "JP8") (pin "3") (pinfunction "3_3") (pintype "passive"))
      (node (ref "JP9") (pin "3") (pinfunction "3_3") (pintype "passive"))
      (node (ref "R_T11.1") (pin "1") (pinfunction "1_1") (pintype "passive"))
    )
    (net (code "74") (name "Net-(LED1-PadA)") (class "Default")
      (node (ref "LED1") (pin "A") (pinfunction "A_A") (pintype "passive"))
      (node (ref "R116") (pin "2") (pinfunction "2_2") (pintype "passive"))
    )
    (net (code "75") (name "Net-(LED2-PadA)") (class "Default")
      (node (ref "LED2") (pin "A") (pinfunction "A_A") (pintype "passive"))
      (node (ref "R115") (pin "2") (pinfunction "2_2") (pintype "passive"))
    )
    (net (code "76") (name "Net-(LED3-PadA)") (class "Default")
      (node (ref "LED3") (pin "A") (pinfunction "A_A") (pintype "passive"))
      (node (ref "R114") (pin "2") (pinfunction "2_2") (pintype "passive"))
    )
    (net (code "77") (name "Net-(LED4-PadA)") (class "Default")
      (node (ref "LED4") (pin "A") (pinfunction "A_A") (pintype "passive"))
      (node (ref "R110") (pin "2") (pinfunction "2_2") (pintype "passive"))
    )
    (net (code "78") (name "Net-(LED5-PadA)") (class "Default")
      (node (ref "LED5") (pin "A") (pinfunction "A_A") (pintype "passive"))
      (node (ref "R111") (pin "2") (pinfunction "2_2") (pintype "passive"))
    )
    (net (code "79") (name "Net-(LED6-PadA)") (class "Default")
      (node (ref "LED6") (pin "A") (pinfunction "A_A") (pintype "passive"))
      (node (ref "R112") (pin "2") (pinfunction "2_2") (pintype "passive"))
    )
    (net (code "80") (name "Net-(LED_ACT-PadA)") (class "Default")
      (node (ref "LED_ACT") (pin "A") (pinfunction "A_A") (pintype "passive"))
      (node (ref "R117") (pin "2") (pinfunction "2_2") (pintype "passive"))
    )
    (net (code "81") (name "Net-(N11-IN+)") (class "Default")
      (node (ref "C_N1.1") (pin "2") (pinfunction "2_2") (pintype "passive"))
      (node (ref "N11") (pin "3") (pinfunction "IN+_3") (pintype "input"))
      (node (ref "R_N1.1") (pin "2") (pinfunction "2_2") (pintype "passive"))
      (node (ref "R_N1.2") (pin "2") (pinfunction "2_2") (pintype "passive"))
      (node (ref "R_N1.3") (pin "2") (pinfunction "2_2") (pintype "passive"))
    )
    (net (code "82") (name "Net-(N11-IN-)") (class "Default")
      (node (ref "C_N1.2") (pin "2") (pinfunction "2_2") (pintype "passive"))
      (node (ref "C_N11.0") (pin "2") (pinfunction "2_2") (pintype "passive"))
      (node (ref "N11") (pin "2") (pinfunction "IN-_2") (pintype "input"))
      (node (ref "R_N1.4") (pin "1") (pinfunction "1_1") (pintype "passive"))
    )
    (net (code "83") (name "Net-(N12-IN+)") (class "Default")
      (node (ref "N12") (pin "3") (pinfunction "IN+_3") (pintype "input"))
      (node (ref "R_N1.5") (pin "1") (pinfunction "1_1") (pintype "passive"))
      (node (ref "R_N1.6") (pin "2") (pinfunction "2_2") (pintype "passive"))
    )
    (net (code "84") (name "Net-(N12-IN-)") (class "Default")
      (node (ref "C_N12.0") (pin "1") (pinfunction "1_1") (pintype "passive"))
      (node (ref "N12") (pin "2") (pinfunction "IN-_2") (pintype "input"))
      (node (ref "R_N1.4") (pin "2") (pinfunction "2_2") (pintype "passive"))
    )
    (net (code "85") (name "Net-(N12-OUT)") (class "Default")
      (node (ref "C_N1.2") (pin "1") (pinfunction "1_1") (pintype "passive"))
      (node (ref "C_N12.0") (pin "2") (pinfunction "2_2") (pintype "passive"))
      (node (ref "N12") (pin "6") (pinfunction "OUT_6") (pintype "output"))
      (node (ref "R_N1.3") (pin "1") (pinfunction "1_1") (pintype "passive"))
    )
    (net (code "86") (name "Net-(N21-IN+)") (class "Default")
      (node (ref "C_N2.1") (pin "2") (pinfunction "2_2") (pintype "passive"))
      (node (ref "N21") (pin "3") (pinfunction "IN+_3") (pintype "input"))
      (node (ref "R_N2.1") (pin "2") (pinfunction "2_2") (pintype "passive"))
      (node (ref "R_N2.2") (pin "2") (pinfunction "2_2") (pintype "passive"))
      (node (ref "R_N2.3") (pin "2") (pinfunction "2_2") (pintype "passive"))
    )
    (net (code "87") (name "Net-(N21-IN-)") (class "Default")
      (node (ref "C_N2.2") (pin "2") (pinfunction "2_2") (pintype "passive"))
      (node (ref "C_N21.0") (pin "2") (pinfunction "2_2") (pintype "passive"))
      (node (ref "N21") (pin "2") (pinfunction "IN-_2") (pintype "input"))
      (node (ref "R_N2.4") (pin "1") (pinfunction "1_1") (pintype "passive"))
    )
    (net (code "88") (name "Net-(N22-IN+)") (class "Default")
      (node (ref "N22") (pin "3") (pinfunction "IN+_3") (pintype "input"))
      (node (ref "R_N2.5") (pin "1") (pinfunction "1_1") (pintype "passive"))
      (node (ref "R_N2.6") (pin "2") (pinfunction "2_2") (pintype "passive"))
    )
    (net (code "89") (name "Net-(N22-IN-)") (class "Default")
      (node (ref "C_N22.0") (pin "1") (pinfunction "1_1") (pintype "passive"))
      (node (ref "N22") (pin "2") (pinfunction "IN-_2") (pintype "input"))
      (node (ref "R_N2.4") (pin "2") (pinfunction "2_2") (pintype "passive"))
    )
    (net (code "90") (name "Net-(N22-OUT)") (class "Default")
      (node (ref "C_N2.2") (pin "1") (pinfunction "1_1") (pintype "passive"))
      (node (ref "C_N22.0") (pin "2") (pinfunction "2_2") (pintype "passive"))
      (node (ref "N22") (pin "6") (pinfunction "OUT_6") (pintype "output"))
      (node (ref "R_N2.3") (pin "1") (pinfunction "1_1") (pintype "passive"))
    )
    (net (code "91") (name "Net-(R_INA1_VAR-A)") (class "Default")
      (node (ref "JP5") (pin "2") (pinfunction "2_2") (pintype "passive"))
      (node (ref "R_INA1_VAR") (pin "1") (pinfunction "A_1") (pintype "passive"))
    )
    (net (code "92") (name "Net-(R_INA1_VAR-S)") (class "Default")
      (node (ref "R_INA1_MIN") (pin "1") (pinfunction "1_1") (pintype "passive"))
      (node (ref "R_INA1_VAR") (pin "2") (pinfunction "S_2") (pintype "passive"))
    )
    (net (code "93") (name "Net-(R_INA2_VAR-A)") (class "Default")
      (node (ref "JP1") (pin "2") (pinfunction "2_2") (pintype "passive"))
      (node (ref "R_INA2_VAR") (pin "1") (pinfunction "A_1") (pintype "passive"))
    )
    (net (code "94") (name "Net-(R_INA2_VAR-S)") (class "Default")
      (node (ref "R_INA2_MIN") (pin "1") (pinfunction "1_1") (pintype "passive"))
      (node (ref "R_INA2_VAR") (pin "2") (pinfunction "S_2") (pintype "passive"))
    )
    (net (code "95") (name "Net-(T11-IN+)") (class "Default")
      (node (ref "C_T11.2") (pin "2") (pinfunction "2_2") (pintype "passive"))
      (node (ref "R_T11.2") (pin "2") (pinfunction "2_2") (pintype "passive"))
      (node (ref "T11") (pin "3") (pinfunction "IN+_3") (pintype "input"))
    )
    (net (code "96") (name "Net-(T11-IN-)") (class "Default")
      (node (ref "C_T11.0") (pin "2") (pinfunction "2_2") (pintype "passive"))
      (node (ref "C_T11.1") (pin "2") (pinfunction "2_2") (pintype "passive"))
      (node (ref "T11") (pin "2") (pinfunction "IN-_2") (pintype "input"))
    )
    (net (code "97") (name "Net-(T12-IN+)") (class "Default")
      (node (ref "C_T12.2") (pin "2") (pinfunction "2_2") (pintype "passive"))
      (node (ref "R_T12.2") (pin "2") (pinfunction "2_2") (pintype "passive"))
      (node (ref "T12") (pin "3") (pinfunction "IN+_3") (pintype "input"))
    )
    (net (code "98") (name "Net-(T12-IN-)") (class "Default")
      (node (ref "C_T12.0") (pin "2") (pinfunction "2_2") (pintype "passive"))
      (node (ref "C_T12.1") (pin "2") (pinfunction "2_2") (pintype "passive"))
      (node (ref "T12") (pin "2") (pinfunction "IN-_2") (pintype "input"))
    )
    (net (code "99") (name "Net-(T21-IN+)") (class "Default")
      (node (ref "C_T21.2") (pin "2") (pinfunction "2_2") (pintype "passive"))
      (node (ref "R_T21.2") (pin "2") (pinfunction "2_2") (pintype "passive"))
      (node (ref "T21") (pin "3") (pinfunction "IN+_3") (pintype "input"))
    )
    (net (code "100") (name "Net-(T21-IN-)") (class "Default")
      (node (ref "C_T21.0") (pin "2") (pinfunction "2_2") (pintype "passive"))
      (node (ref "C_T21.1") (pin "2") (pinfunction "2_2") (pintype "passive"))
      (node (ref "T21") (pin "2") (pinfunction "IN-_2") (pintype "input"))
    )
    (net (code "101") (name "Net-(T22-IN+)") (class "Default")
      (node (ref "C_T22.2") (pin "2") (pinfunction "2_2") (pintype "passive"))
      (node (ref "R_T22.2") (pin "2") (pinfunction "2_2") (pintype "passive"))
      (node (ref "T22") (pin "3") (pinfunction "IN+_3") (pintype "input"))
    )
    (net (code "102") (name "Net-(T22-IN-)") (class "Default")
      (node (ref "C_T22.0") (pin "2") (pinfunction "2_2") (pintype "passive"))
      (node (ref "C_T22.1") (pin "2") (pinfunction "2_2") (pintype "passive"))
      (node (ref "T22") (pin "2") (pinfunction "IN-_2") (pintype "input"))
    )
    (net (code "103") (name "Net-(U$1-P1.0)") (class "Default")
      (node (ref "P1") (pin "5") (pinfunction "5_5") (pintype "passive"))
      (node (ref "U$1") (pin "37") (pinfunction "P1.0_37") (pintype "bidirectional"))
    )
    (net (code "104") (name "Net-(U$1-P1.1)") (class "Default")
      (node (ref "P1") (pin "4") (pinfunction "4_4") (pintype "passive"))
      (node (ref "U$1") (pin "36") (pinfunction "P1.1_36") (pintype "bidirectional"))
    )
    (net (code "105") (name "Net-(U$1-P1.3)") (class "Default")
      (node (ref "P1") (pin "3") (pinfunction "3_3") (pintype "passive"))
      (node (ref "U$1") (pin "34") (pinfunction "P1.3_34") (pintype "bidirectional"))
    )
    (net (code "106") (name "Net-(U$1-P1.6)") (class "Default")
      (node (ref "P1") (pin "2") (pinfunction "2_2") (pintype "passive"))
      (node (ref "U$1") (pin "40") (pinfunction "P1.6_40") (pintype "bidirectional"))
    )
    (net (code "107") (name "Net-(U$1-P1.7)") (class "Default")
      (node (ref "P1") (pin "1") (pinfunction "1_1") (pintype "passive"))
      (node (ref "U$1") (pin "41") (pinfunction "P1.7_41") (pintype "bidirectional"))
    )
    (net (code "108") (name "Net-(U$1-P2.0)") (class "Default")
      (node (ref "P2") (pin "8") (pinfunction "8_8") (pintype "passive"))
      (node (ref "U$1") (pin "42") (pinfunction "P2.0_42") (pintype "bidirectional"))
    )
    (net (code "109") (name "Net-(U$1-P2.1)") (class "Default")
      (node (ref "P2") (pin "7") (pinfunction "7_7") (pintype "passive"))
      (node (ref "U$1") (pin "43") (pinfunction "P2.1_43") (pintype "bidirectional"))
    )
    (net (code "110") (name "Net-(U$1-P2.2)") (class "Default")
      (node (ref "P2") (pin "6") (pinfunction "6_6") (pintype "passive"))
      (node (ref "U$1") (pin "44") (pinfunction "P2.2_44") (pintype "bidirectional"))
    )
    (net (code "111") (name "Net-(U$1-P2.3)") (class "Default")
      (node (ref "P2") (pin "5") (pinfunction "5_5") (pintype "passive"))
      (node (ref "U$1") (pin "45") (pinfunction "P2.3_45") (pintype "bidirectional"))
    )
    (net (code "112") (name "Net-(U$1-P2.4)") (class "Default")
      (node (ref "P2") (pin "4") (pinfunction "4_4") (pintype "passive"))
      (node (ref "U$1") (pin "47") (pinfunction "P2.4_47") (pintype "bidirectional"))
    )
    (net (code "113") (name "Net-(U$1-P2.5)") (class "Default")
      (node (ref "P2") (pin "3") (pinfunction "3_3") (pintype "passive"))
      (node (ref "U$1") (pin "48") (pinfunction "P2.5_48") (pintype "bidirectional"))
    )
    (net (code "114") (name "Net-(U$1-P2.6)") (class "Default")
      (node (ref "P2") (pin "2") (pinfunction "2_2") (pintype "passive"))
      (node (ref "U$1") (pin "49") (pinfunction "P2.6_49") (pintype "bidirectional"))
    )
    (net (code "115") (name "Net-(U$1-P2.7)") (class "Default")
      (node (ref "P2") (pin "1") (pinfunction "1_1") (pintype "passive"))
      (node (ref "U$1") (pin "50") (pinfunction "P2.7_50") (pintype "bidirectional"))
    )
    (net (code "116") (name "Net-(U$1-P3.0)") (class "Default")
      (node (ref "P3") (pin "8") (pinfunction "8_8") (pintype "passive"))
      (node (ref "U$1") (pin "51") (pinfunction "P3.0_51") (pintype "bidirectional"))
    )
    (net (code "117") (name "Net-(U$1-P3.1)") (class "Default")
      (node (ref "P3") (pin "7") (pinfunction "7_7") (pintype "passive"))
      (node (ref "U$1") (pin "52") (pinfunction "P3.1_52") (pintype "bidirectional"))
    )
    (net (code "118") (name "Net-(U$1-P3.2)") (class "Default")
      (node (ref "P3") (pin "6") (pinfunction "6_6") (pintype "passive"))
      (node (ref "U$1") (pin "53") (pinfunction "P3.2_53") (pintype "bidirectional"))
    )
    (net (code "119") (name "Net-(U$1-P3.3)") (class "Default")
      (node (ref "P3") (pin "5") (pinfunction "5_5") (pintype "passive"))
      (node (ref "U$1") (pin "54") (pinfunction "P3.3_54") (pintype "bidirectional"))
    )
    (net (code "120") (name "Net-(U$1-P3.4)") (class "Default")
      (node (ref "P3") (pin "4") (pinfunction "4_4") (pintype "passive"))
      (node (ref "U$1") (pin "55") (pinfunction "P3.4_55") (pintype "bidirectional"))
    )
    (net (code "121") (name "Net-(U$1-P3.5)") (class "Default")
      (node (ref "P3") (pin "3") (pinfunction "3_3") (pintype "passive"))
      (node (ref "U$1") (pin "56") (pinfunction "P3.5_56") (pintype "bidirectional"))
    )
    (net (code "122") (name "Net-(U$1-P3.6)") (class "Default")
      (node (ref "P3") (pin "2") (pinfunction "2_2") (pintype "passive"))
      (node (ref "U$1") (pin "57") (pinfunction "P3.6_57") (pintype "bidirectional"))
    )
    (net (code "123") (name "Net-(U$1-P3.7)") (class "Default")
      (node (ref "P3") (pin "1") (pinfunction "1_1") (pintype "passive"))
      (node (ref "U$1") (pin "58") (pinfunction "P3.7_58") (pintype "bidirectional"))
    )
    (net (code "124") (name "Net-(U$1-P4.0)") (class "Default")
      (node (ref "P4") (pin "1") (pinfunction "1_1") (pintype "passive"))
      (node (ref "U$1") (pin "59") (pinfunction "P4.0_59") (pintype "bidirectional"))
    )
    (net (code "125") (name "Net-(U$1-P4.1)") (class "Default")
      (node (ref "P4") (pin "2") (pinfunction "2_2") (pintype "passive"))
      (node (ref "U$1") (pin "60") (pinfunction "P4.1_60") (pintype "bidirectional"))
    )
    (net (code "126") (name "Net-(U$1-P4.2)") (class "Default")
      (node (ref "P4") (pin "3") (pinfunction "3_3") (pintype "passive"))
      (node (ref "U$1") (pin "61") (pinfunction "P4.2_61") (pintype "bidirectional"))
    )
    (net (code "127") (name "Net-(U$1-P4.3)") (class "Default")
      (node (ref "P4") (pin "4") (pinfunction "4_4") (pintype "passive"))
      (node (ref "U$1") (pin "62") (pinfunction "P4.3_62") (pintype "bidirectional"))
    )
    (net (code "128") (name "Net-(U$1-P4.4)") (class "Default")
      (node (ref "P4") (pin "5") (pinfunction "5_5") (pintype "passive"))
      (node (ref "U$1") (pin "63") (pinfunction "P4.4_63") (pintype "bidirectional"))
    )
    (net (code "129") (name "Net-(U$1-P4.5)") (class "Default")
      (node (ref "P4") (pin "6") (pinfunction "6_6") (pintype "passive"))
      (node (ref "U$1") (pin "64") (pinfunction "P4.5_64") (pintype "bidirectional"))
    )
    (net (code "130") (name "Net-(U$1-P4.6)") (class "Default")
      (node (ref "P4") (pin "7") (pinfunction "7_7") (pintype "passive"))
      (node (ref "U$1") (pin "65") (pinfunction "P4.6_65") (pintype "bidirectional"))
    )
    (net (code "131") (name "Net-(U$1-P4.7)") (class "Default")
      (node (ref "P4") (pin "8") (pinfunction "8_8") (pintype "passive"))
      (node (ref "U$1") (pin "66") (pinfunction "P4.7_66") (pintype "bidirectional"))
    )
    (net (code "132") (name "Net-(U$1-P5.0)") (class "Default")
      (node (ref "P5") (pin "1") (pinfunction "1_1") (pintype "passive"))
      (node (ref "U$1") (pin "67") (pinfunction "P5.0_67") (pintype "bidirectional"))
    )
    (net (code "133") (name "Net-(U$1-P5.1)") (class "Default")
      (node (ref "P5") (pin "2") (pinfunction "2_2") (pintype "passive"))
      (node (ref "U$1") (pin "68") (pinfunction "P5.1_68") (pintype "bidirectional"))
    )
    (net (code "134") (name "Net-(U$1-P5.2)") (class "Default")
      (node (ref "P5") (pin "3") (pinfunction "3_3") (pintype "passive"))
      (node (ref "U$1") (pin "69") (pinfunction "P5.2_69") (pintype "bidirectional"))
    )
    (net (code "135") (name "Net-(U$1-P5.3)") (class "Default")
      (node (ref "P5") (pin "4") (pinfunction "4_4") (pintype "passive"))
      (node (ref "U$1") (pin "70") (pinfunction "P5.3_70") (pintype "bidirectional"))
    )
    (net (code "136") (name "Net-(U$1-P5.4)") (class "Default")
      (node (ref "P5") (pin "5") (pinfunction "5_5") (pintype "passive"))
      (node (ref "U$1") (pin "71") (pinfunction "P5.4_71") (pintype "bidirectional"))
    )
    (net (code "137") (name "Net-(U$1-P5.5)") (class "Default")
      (node (ref "P5") (pin "6") (pinfunction "6_6") (pintype "passive"))
      (node (ref "U$1") (pin "72") (pinfunction "P5.5_72") (pintype "bidirectional"))
    )
    (net (code "138") (name "Net-(U$1-P5.6)") (class "Default")
      (node (ref "P5") (pin "7") (pinfunction "7_7") (pintype "passive"))
      (node (ref "U$1") (pin "73") (pinfunction "P5.6_73") (pintype "bidirectional"))
    )
    (net (code "139") (name "Net-(U$1-P5.7)") (class "Default")
      (node (ref "P5") (pin "8") (pinfunction "8_8") (pintype "passive"))
      (node (ref "U$1") (pin "74") (pinfunction "P5.7_74") (pintype "bidirectional"))
    )
    (net (code "140") (name "Net-(U$1-P6.1)") (class "Default")
      (node (ref "P6") (pin "2") (pinfunction "2_2") (pintype "passive"))
      (node (ref "U$1") (pin "78") (pinfunction "P6.1_78") (pintype "bidirectional"))
    )
    (net (code "141") (name "Net-(U$1-P6.2)") (class "Default")
      (node (ref "P6") (pin "3") (pinfunction "3_3") (pintype "passive"))
      (node (ref "U$1") (pin "79") (pinfunction "P6.2_79") (pintype "bidirectional"))
    )
    (net (code "142") (name "Net-(U$1-P6.3)") (class "Default")
      (node (ref "P6") (pin "4") (pinfunction "4_4") (pintype "passive"))
      (node (ref "U$1") (pin "80") (pinfunction "P6.3_80") (pintype "bidirectional"))
    )
    (net (code "143") (name "Net-(U$1-P6.4)") (class "Default")
      (node (ref "P6") (pin "5") (pinfunction "5_5") (pintype "passive"))
      (node (ref "U$1") (pin "81") (pinfunction "P6.4_81") (pintype "bidirectional"))
    )
    (net (code "144") (name "Net-(U$1-P6.5)") (class "Default")
      (node (ref "P6") (pin "6") (pinfunction "6_6") (pintype "passive"))
      (node (ref "U$1") (pin "82") (pinfunction "P6.5_82") (pintype "bidirectional"))
    )
    (net (code "145") (name "P6.0") (class "Default")
      (node (ref "BTN_3") (pin "2") (pinfunction "S_2") (pintype "passive"))
      (node (ref "P6") (pin "1") (pinfunction "1_1") (pintype "passive"))
      (node (ref "R122") (pin "2") (pinfunction "2_2") (pintype "passive"))
      (node (ref "U$1") (pin "77") (pinfunction "P6.0_77") (pintype "bidirectional"))
    )
    (net (code "146") (name "REF") (class "Default")
      (node (ref "INA_1") (pin "5") (pinfunction "REF_5") (pintype "bidirectional"))
      (node (ref "INA_2") (pin "5") (pinfunction "REF_5") (pintype "bidirectional"))
      (node (ref "JP12") (pin "1") (pinfunction "1_1") (pintype "passive"))
      (node (ref "JP13") (pin "1") (pinfunction "1_1") (pintype "passive"))
    )
    (net (code "147") (name "RESET") (class "Default")
      (node (ref "C110") (pin "2") (pinfunction "2_2") (pintype "passive"))
      (node (ref "JTAG") (pin "11") (pinfunction "11_11") (pintype "passive"))
      (node (ref "R101") (pin "2") (pinfunction "2_2") (pintype "passive"))
      (node (ref "RESET") (pin "1") (pinfunction "P_1") (pintype "passive"))
      (node (ref "U$1") (pin "100") (pinfunction "RST/NMI/SBTDIO_100") (pintype "bidirectional"))
    )
    (net (code "148") (name "RS+") (class "Default")
      (node (ref "INA_1") (pin "3") (pinfunction "+IN_3") (pintype "bidirectional"))
      (node (ref "J1") (pin "4") (pinfunction "4_4") (pintype "passive"))
      (node (ref "R_RS") (pin "1") (pinfunction "1_1") (pintype "passive"))
    )
    (net (code "149") (name "RS-") (class "Default")
      (node (ref "INA_1") (pin "2") (pinfunction "-IN_2") (pintype "bidirectional"))
      (node (ref "J1") (pin "1") (pinfunction "1_1") (pintype "passive"))
      (node (ref "R_RS") (pin "2") (pinfunction "2_2") (pintype "passive"))
    )
    (net (code "150") (name "RS_TO_ADC1") (class "Default")
      (node (ref "JP10") (pin "3") (pinfunction "3_3") (pintype "passive"))
      (node (ref "JP11") (pin "1") (pinfunction "1_1") (pintype "passive"))
      (node (ref "JP15") (pin "2") (pinfunction "2_2") (pintype "passive"))
      (node (ref "JP9") (pin "5") (pinfunction "5_5") (pintype "passive"))
      (node (ref "TP5_H1") (pin "TP") (pinfunction "TP_TP") (pintype "input"))
      (node (ref "TP6_T1") (pin "TP") (pinfunction "TP_TP") (pintype "input"))
      (node (ref "TP7_N1") (pin "TP") (pinfunction "TP_TP") (pintype "input"))
    )
    (net (code "151") (name "RTCCLK") (class "Default")
      (node (ref "CLOCK") (pin "2") (pinfunction "2_2") (pintype "passive"))
      (node (ref "U$1") (pin "94") (pinfunction "P8.1_94") (pintype "bidirectional"))
    )
    (net (code "152") (name "SD_IN_1P") (class "Default")
      (node (ref "JP15") (pin "1") (pinfunction "1_1") (pintype "passive"))
      (node (ref "U$1") (pin "1") (pinfunction "SD0P0_1") (pintype "bidirectional"))
    )
    (net (code "153") (name "SD_IN_2P") (class "Default")
      (node (ref "JP16") (pin "1") (pinfunction "1_1") (pintype "passive"))
      (node (ref "U$1") (pin "12") (pinfunction "SD4P0_12") (pintype "bidirectional"))
    )
    (net (code "154") (name "SMCLK") (class "Default")
      (node (ref "CLOCK") (pin "5") (pinfunction "5_5") (pintype "passive"))
      (node (ref "U$1") (pin "32") (pinfunction "P1.5_32") (pintype "bidirectional"))
    )
    (net (code "155") (name "T1_OUT") (class "Default")
      (node (ref "C_T12.0") (pin "1") (pinfunction "1_1") (pintype "passive"))
      (node (ref "JP10") (pin "2") (pinfunction "2_2") (pintype "passive"))
      (node (ref "JP10") (pin "4") (pinfunction "4_4") (pintype "passive"))
      (node (ref "JP10") (pin "6") (pinfunction "6_6") (pintype "passive"))
      (node (ref "T12") (pin "6") (pinfunction "OUT_6") (pintype "output"))
      (node (ref "TP3") (pin "TP") (pinfunction "TP_TP") (pintype "input"))
    )
    (net (code "156") (name "T2_OUT") (class "Default")
      (node (ref "C_T22.0") (pin "1") (pinfunction "1_1") (pintype "passive"))
      (node (ref "JP4") (pin "2") (pinfunction "2_2") (pintype "passive"))
      (node (ref "JP4") (pin "4") (pinfunction "4_4") (pintype "passive"))
      (node (ref "JP4") (pin "6") (pinfunction "6_6") (pintype "passive"))
      (node (ref "T22") (pin "6") (pinfunction "OUT_6") (pintype "output"))
      (node (ref "TP10") (pin "TP") (pinfunction "TP_TP") (pintype "input"))
    )
    (net (code "157") (name "T11_OUT") (class "Default")
      (node (ref "C_T11.0") (pin "1") (pinfunction "1_1") (pintype "passive"))
      (node (ref "R_T12.1") (pin "1") (pinfunction "1_1") (pintype "passive"))
      (node (ref "T11") (pin "6") (pinfunction "OUT_6") (pintype "output"))
      (node (ref "TP16") (pin "TP") (pinfunction "TP_TP") (pintype "input"))
    )
    (net (code "158") (name "T21_OUT") (class "Default")
      (node (ref "C_T21.0") (pin "1") (pinfunction "1_1") (pintype "passive"))
      (node (ref "R_T22.1") (pin "1") (pinfunction "1_1") (pintype "passive"))
      (node (ref "T21") (pin "6") (pinfunction "OUT_6") (pintype "output"))
      (node (ref "TP18") (pin "TP") (pinfunction "TP_TP") (pintype "input"))
    )
    (net (code "159") (name "TCK") (class "Default")
      (node (ref "JTAG") (pin "7") (pinfunction "7_7") (pintype "passive"))
      (node (ref "U$1") (pin "99") (pinfunction "PJ.3/TCK_99") (pintype "bidirectional"))
    )
    (net (code "160") (name "TDI") (class "Default")
      (node (ref "JTAG") (pin "3") (pinfunction "3_3") (pintype "passive"))
      (node (ref "U$1") (pin "97") (pinfunction "PJ.1/TDI/TCLK_97") (pintype "bidirectional"))
    )
    (net (code "161") (name "TDO") (class "Default")
      (node (ref "JTAG") (pin "1") (pinfunction "1_1") (pintype "passive"))
      (node (ref "U$1") (pin "96") (pinfunction "PJ.0/TDO_96") (pintype "bidirectional"))
    )
    (net (code "162") (name "TEST{slash}SBWTCK") (class "Default")
      (node (ref "JTAG") (pin "8") (pinfunction "8_8") (pintype "passive"))
      (node (ref "U$1") (pin "95") (pinfunction "TEST/SBWTCK_95") (pintype "bidirectional"))
    )
    (net (code "163") (name "TMS") (class "Default")
      (node (ref "JTAG") (pin "5") (pinfunction "5_5") (pintype "passive"))
      (node (ref "U$1") (pin "98") (pinfunction "PJ.2/TMS_98") (pintype "bidirectional"))
    )
    (net (code "164") (name "VASYS1{slash}2") (class "Default")
      (node (ref "C22") (pin "1") (pinfunction "1_1") (pintype "passive"))
      (node (ref "C23") (pin "1") (pinfunction "1_1") (pintype "passive"))
      (node (ref "C28") (pin "1") (pinfunction "1_1") (pintype "passive"))
      (node (ref "C32") (pin "1") (pinfunction "1_1") (pintype "passive"))
      (node (ref "U$1") (pin "20") (pinfunction "VASYS1_20") (pintype "bidirectional"))
      (node (ref "U$1") (pin "9") (pinfunction "VASYS2_9") (pintype "bidirectional"))
    )
    (net (code "165") (name "VCORE") (class "Default")
      (node (ref "C38") (pin "1") (pinfunction "1_1") (pintype "passive"))
      (node (ref "U$1") (pin "26") (pinfunction "VCORE_26") (pintype "bidirectional"))
    )
    (net (code "166") (name "VREF") (class "Default")
      (node (ref "C30") (pin "1") (pinfunction "1_1") (pintype "passive"))
      (node (ref "U$1") (pin "11") (pinfunction "VREF_11") (pintype "bidirectional"))
    )
    (net (code "167") (name "XIN") (class "Default")
      (node (ref "C100") (pin "1") (pinfunction "1_1") (pintype "passive"))
      (node (ref "U$1") (pin "27") (pinfunction "XIN_27") (pintype "bidirectional"))
      (node (ref "XT1") (pin "P2") (pinfunction "2_P2") (pintype "bidirectional"))
    )
    (net (code "168") (name "XOUT") (class "Default")
      (node (ref "C101") (pin "1") (pinfunction "1_1") (pintype "passive"))
      (node (ref "U$1") (pin "28") (pinfunction "XOUT_28") (pintype "bidirectional"))
      (node (ref "XT1") (pin "P1") (pinfunction "1_P1") (pintype "bidirectional"))
    )
    (net (code "169") (name "unconnected-(H11-NC1-Pad1)") (class "Default")
      (node (ref "H11") (pin "1") (pinfunction "NC1_1") (pintype "no_connect"))
    )
    (net (code "170") (name "unconnected-(H11-NC2-Pad5)") (class "Default")
      (node (ref "H11") (pin "5") (pinfunction "NC2_5") (pintype "no_connect"))
    )
    (net (code "171") (name "unconnected-(H11-NC3-Pad8)") (class "Default")
      (node (ref "H11") (pin "8") (pinfunction "NC3_8") (pintype "no_connect"))
    )
    (net (code "172") (name "unconnected-(H12-NC1-Pad1)") (class "Default")
      (node (ref "H12") (pin "1") (pinfunction "NC1_1") (pintype "no_connect"))
    )
    (net (code "173") (name "unconnected-(H12-NC2-Pad5)") (class "Default")
      (node (ref "H12") (pin "5") (pinfunction "NC2_5") (pintype "no_connect"))
    )
    (net (code "174") (name "unconnected-(H12-NC3-Pad8)") (class "Default")
      (node (ref "H12") (pin "8") (pinfunction "NC3_8") (pintype "no_connect"))
    )
    (net (code "175") (name "unconnected-(H21-NC1-Pad1)") (class "Default")
      (node (ref "H21") (pin "1") (pinfunction "NC1_1") (pintype "no_connect"))
    )
    (net (code "176") (name "unconnected-(H21-NC2-Pad5)") (class "Default")
      (node (ref "H21") (pin "5") (pinfunction "NC2_5") (pintype "no_connect"))
    )
    (net (code "177") (name "unconnected-(H21-NC3-Pad8)") (class "Default")
      (node (ref "H21") (pin "8") (pinfunction "NC3_8") (pintype "no_connect"))
    )
    (net (code "178") (name "unconnected-(H22-NC1-Pad1)") (class "Default")
      (node (ref "H22") (pin "1") (pinfunction "NC1_1") (pintype "no_connect"))
    )
    (net (code "179") (name "unconnected-(H22-NC2-Pad5)") (class "Default")
      (node (ref "H22") (pin "5") (pinfunction "NC2_5") (pintype "no_connect"))
    )
    (net (code "180") (name "unconnected-(H22-NC3-Pad8)") (class "Default")
      (node (ref "H22") (pin "8") (pinfunction "NC3_8") (pintype "no_connect"))
    )
    (net (code "181") (name "unconnected-(JTAG-Pad6)") (class "Default")
      (node (ref "JTAG") (pin "6") (pinfunction "6_6") (pintype "passive"))
    )
    (net (code "182") (name "unconnected-(JTAG-Pad10)") (class "Default")
      (node (ref "JTAG") (pin "10") (pinfunction "10_10") (pintype "passive"))
    )
    (net (code "183") (name "unconnected-(JTAG-Pad12)") (class "Default")
      (node (ref "JTAG") (pin "12") (pinfunction "12_12") (pintype "passive"))
    )
    (net (code "184") (name "unconnected-(JTAG-Pad13)") (class "Default")
      (node (ref "JTAG") (pin "13") (pinfunction "13_13") (pintype "passive"))
    )
    (net (code "185") (name "unconnected-(JTAG-Pad14)") (class "Default")
      (node (ref "JTAG") (pin "14") (pinfunction "14_14") (pintype "passive"))
    )
    (net (code "186") (name "unconnected-(N11-NC1-Pad1)") (class "Default")
      (node (ref "N11") (pin "1") (pinfunction "NC1_1") (pintype "no_connect"))
    )
    (net (code "187") (name "unconnected-(N11-NC2-Pad5)") (class "Default")
      (node (ref "N11") (pin "5") (pinfunction "NC2_5") (pintype "no_connect"))
    )
    (net (code "188") (name "unconnected-(N11-NC3-Pad8)") (class "Default")
      (node (ref "N11") (pin "8") (pinfunction "NC3_8") (pintype "no_connect"))
    )
    (net (code "189") (name "unconnected-(N12-NC1-Pad1)") (class "Default")
      (node (ref "N12") (pin "1") (pinfunction "NC1_1") (pintype "no_connect"))
    )
    (net (code "190") (name "unconnected-(N12-NC2-Pad5)") (class "Default")
      (node (ref "N12") (pin "5") (pinfunction "NC2_5") (pintype "no_connect"))
    )
    (net (code "191") (name "unconnected-(N12-NC3-Pad8)") (class "Default")
      (node (ref "N12") (pin "8") (pinfunction "NC3_8") (pintype "no_connect"))
    )
    (net (code "192") (name "unconnected-(N21-NC1-Pad1)") (class "Default")
      (node (ref "N21") (pin "1") (pinfunction "NC1_1") (pintype "no_connect"))
    )
    (net (code "193") (name "unconnected-(N21-NC2-Pad5)") (class "Default")
      (node (ref "N21") (pin "5") (pinfunction "NC2_5") (pintype "no_connect"))
    )
    (net (code "194") (name "unconnected-(N21-NC3-Pad8)") (class "Default")
      (node (ref "N21") (pin "8") (pinfunction "NC3_8") (pintype "no_connect"))
    )
    (net (code "195") (name "unconnected-(N22-NC1-Pad1)") (class "Default")
      (node (ref "N22") (pin "1") (pinfunction "NC1_1") (pintype "no_connect"))
    )
    (net (code "196") (name "unconnected-(N22-NC2-Pad5)") (class "Default")
      (node (ref "N22") (pin "5") (pinfunction "NC2_5") (pintype "no_connect"))
    )
    (net (code "197") (name "unconnected-(N22-NC3-Pad8)") (class "Default")
      (node (ref "N22") (pin "8") (pinfunction "NC3_8") (pintype "no_connect"))
    )
    (net (code "198") (name "unconnected-(R_INA1_VAR-E-Pad3)") (class "Default")
      (node (ref "R_INA1_VAR") (pin "3") (pinfunction "E_3") (pintype "passive"))
    )
    (net (code "199") (name "unconnected-(R_INA2_VAR-E-Pad3)") (class "Default")
      (node (ref "R_INA2_VAR") (pin "3") (pinfunction "E_3") (pintype "passive"))
    )
    (net (code "200") (name "unconnected-(T11-NC1-Pad1)") (class "Default")
      (node (ref "T11") (pin "1") (pinfunction "NC1_1") (pintype "no_connect"))
    )
    (net (code "201") (name "unconnected-(T11-NC2-Pad5)") (class "Default")
      (node (ref "T11") (pin "5") (pinfunction "NC2_5") (pintype "no_connect"))
    )
    (net (code "202") (name "unconnected-(T11-NC3-Pad8)") (class "Default")
      (node (ref "T11") (pin "8") (pinfunction "NC3_8") (pintype "no_connect"))
    )
    (net (code "203") (name "unconnected-(T12-NC1-Pad1)") (class "Default")
      (node (ref "T12") (pin "1") (pinfunction "NC1_1") (pintype "no_connect"))
    )
    (net (code "204") (name "unconnected-(T12-NC2-Pad5)") (class "Default")
      (node (ref "T12") (pin "5") (pinfunction "NC2_5") (pintype "no_connect"))
    )
    (net (code "205") (name "unconnected-(T12-NC3-Pad8)") (class "Default")
      (node (ref "T12") (pin "8") (pinfunction "NC3_8") (pintype "no_connect"))
    )
    (net (code "206") (name "unconnected-(T21-NC1-Pad1)") (class "Default")
      (node (ref "T21") (pin "1") (pinfunction "NC1_1") (pintype "no_connect"))
    )
    (net (code "207") (name "unconnected-(T21-NC2-Pad5)") (class "Default")
      (node (ref "T21") (pin "5") (pinfunction "NC2_5") (pintype "no_connect"))
    )
    (net (code "208") (name "unconnected-(T21-NC3-Pad8)") (class "Default")
      (node (ref "T21") (pin "8") (pinfunction "NC3_8") (pintype "no_connect"))
    )
    (net (code "209") (name "unconnected-(T22-NC1-Pad1)") (class "Default")
      (node (ref "T22") (pin "1") (pinfunction "NC1_1") (pintype "no_connect"))
    )
    (net (code "210") (name "unconnected-(T22-NC2-Pad5)") (class "Default")
      (node (ref "T22") (pin "5") (pinfunction "NC2_5") (pintype "no_connect"))
    )
    (net (code "211") (name "unconnected-(T22-NC3-Pad8)") (class "Default")
      (node (ref "T22") (pin "8") (pinfunction "NC3_8") (pintype "no_connect"))
    )
    (net (code "212") (name "unconnected-(U$1-RTCCAP0-Pad31)") (class "Default")
      (node (ref "U$1") (pin "31") (pinfunction "RTCCAP0_31") (pintype "bidirectional"))
    )
    (net (code "213") (name "unconnected-(U$1-RTCCAP1-Pad30)") (class "Default")
      (node (ref "U$1") (pin "30") (pinfunction "RTCCAP1_30") (pintype "bidirectional"))
    )
  )
)
